# CANTensegrityBoard.net
KiCad netlist of a schematic drawn in EAGLE
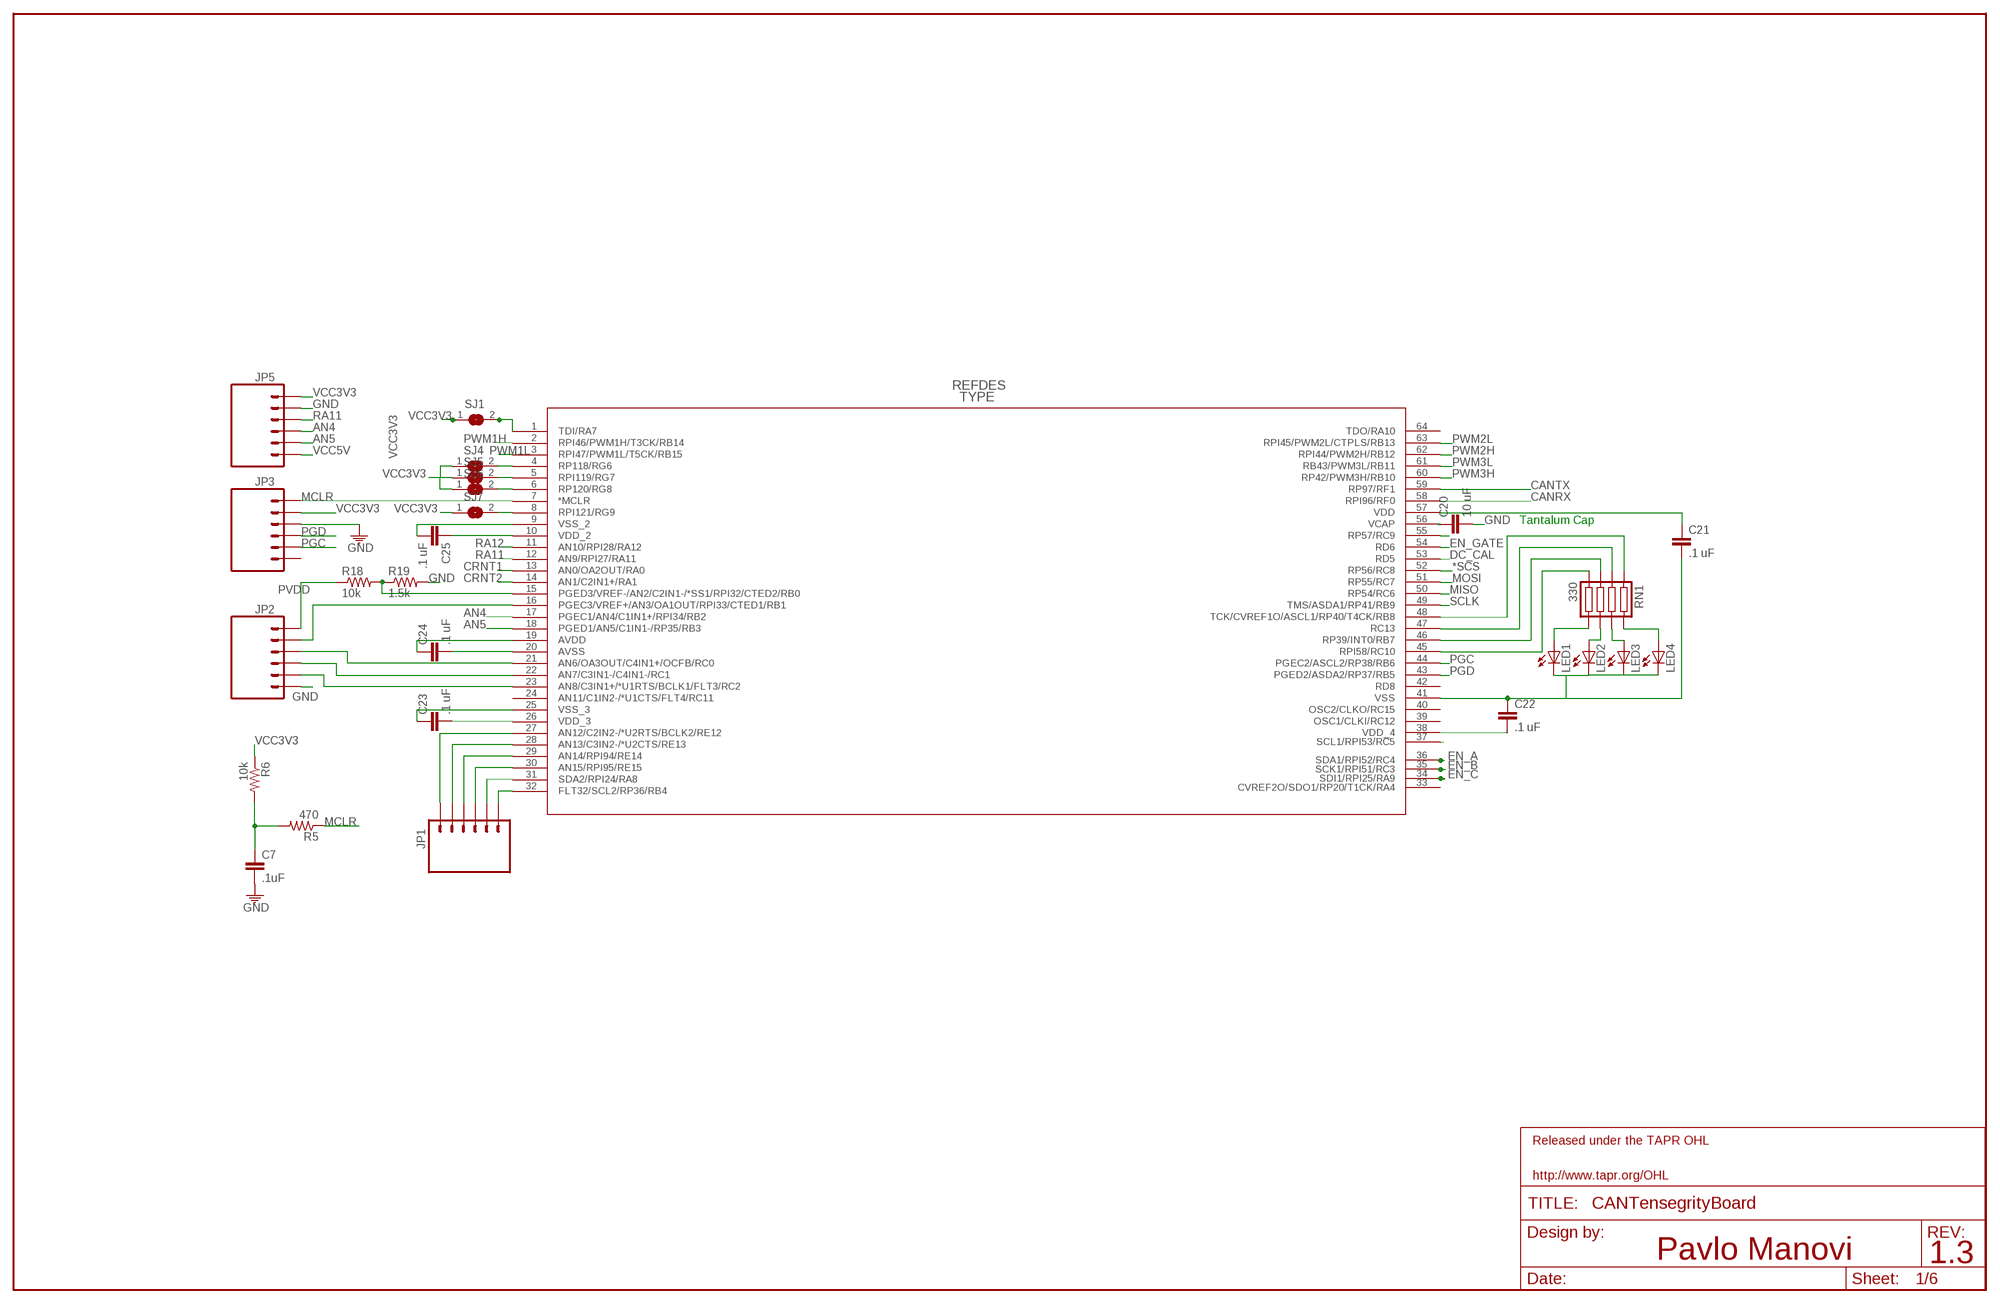
[diagram p0: schematic, sheet 1]
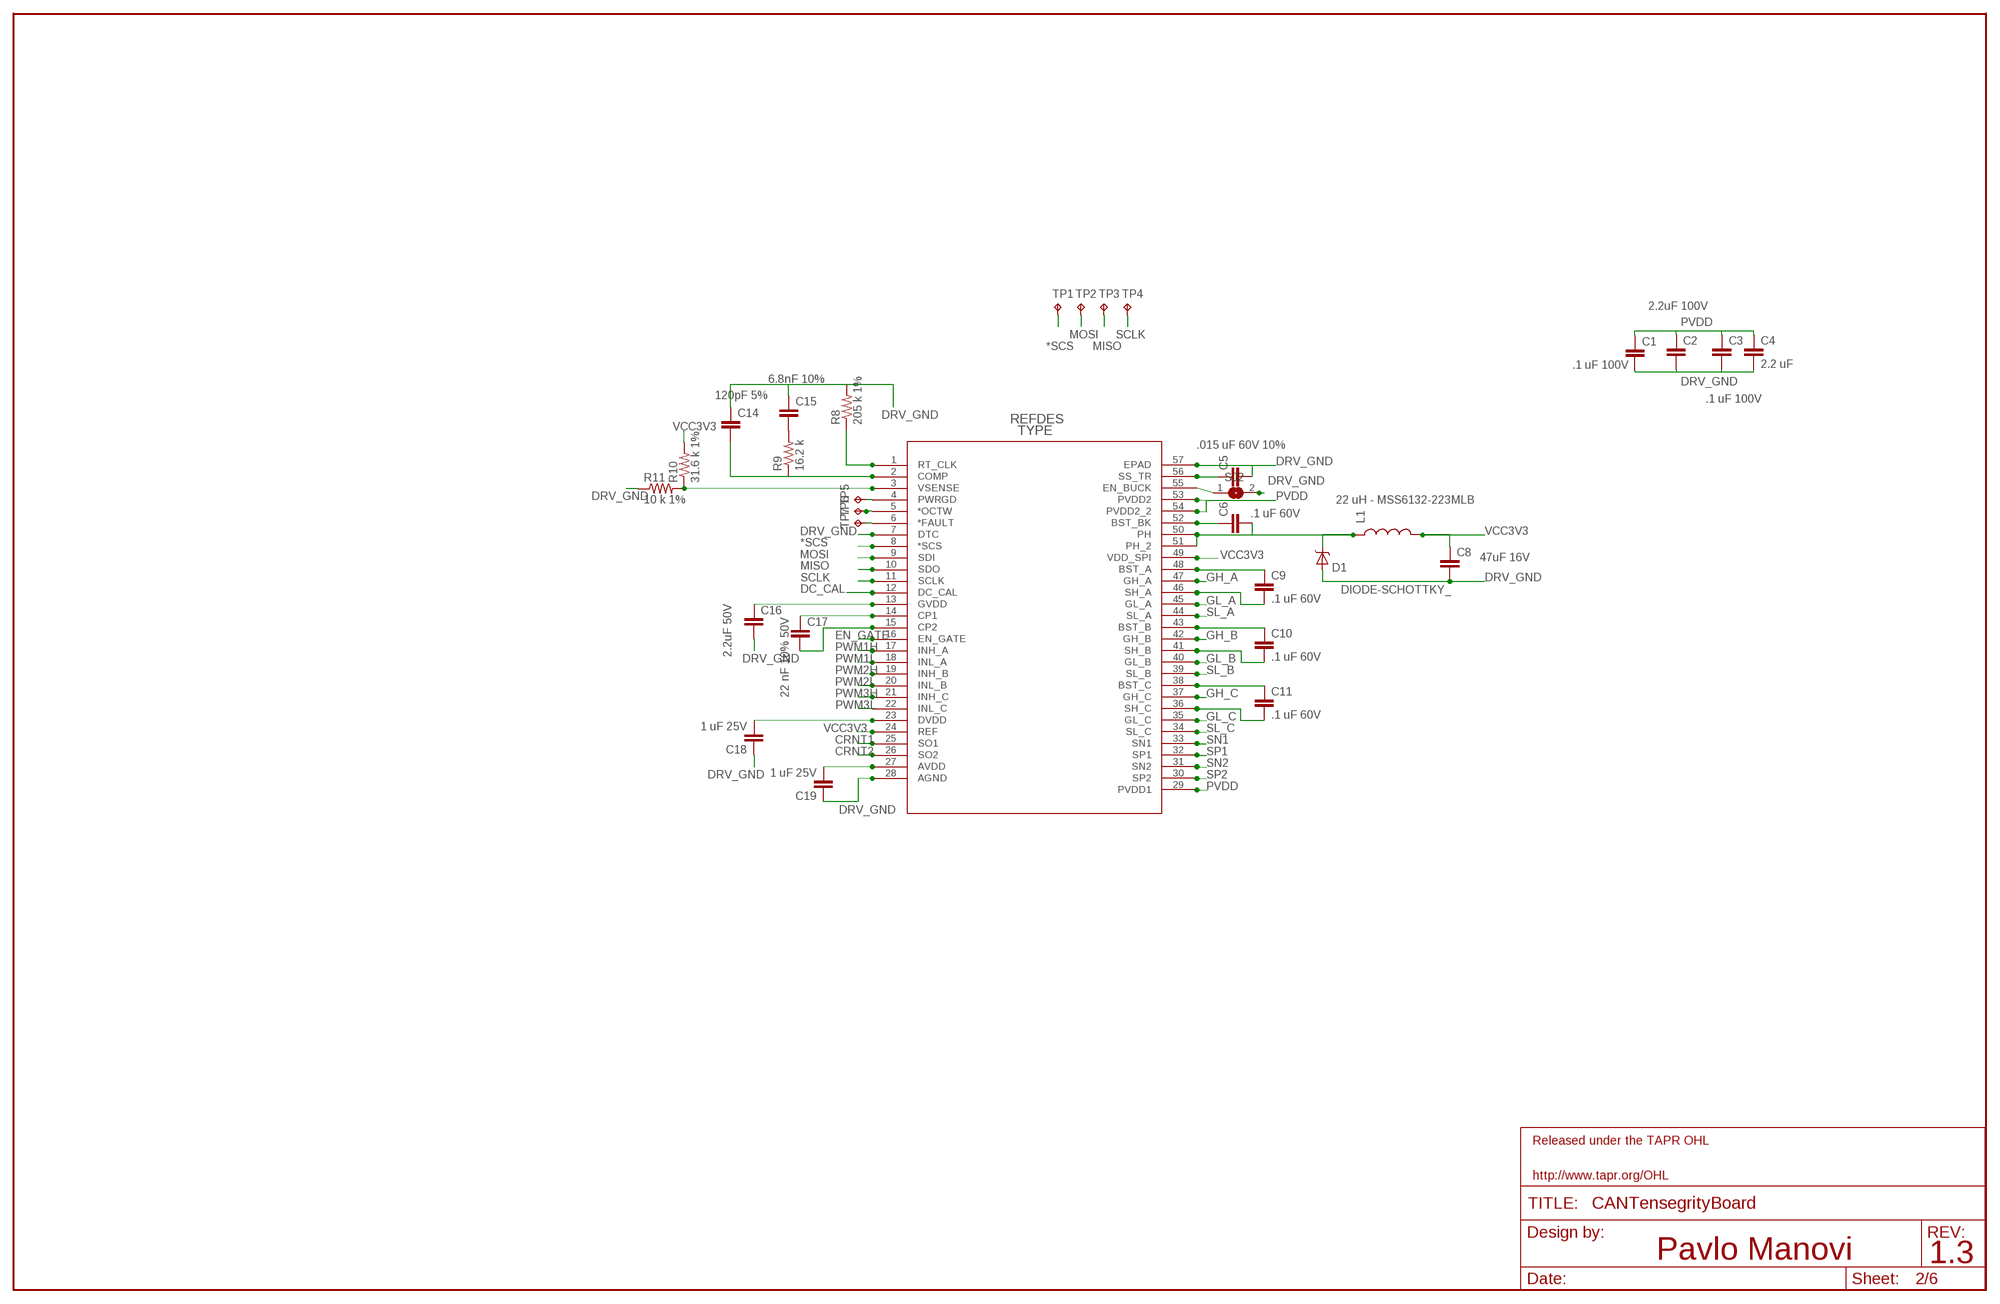
[diagram p1: schematic, sheet 2]
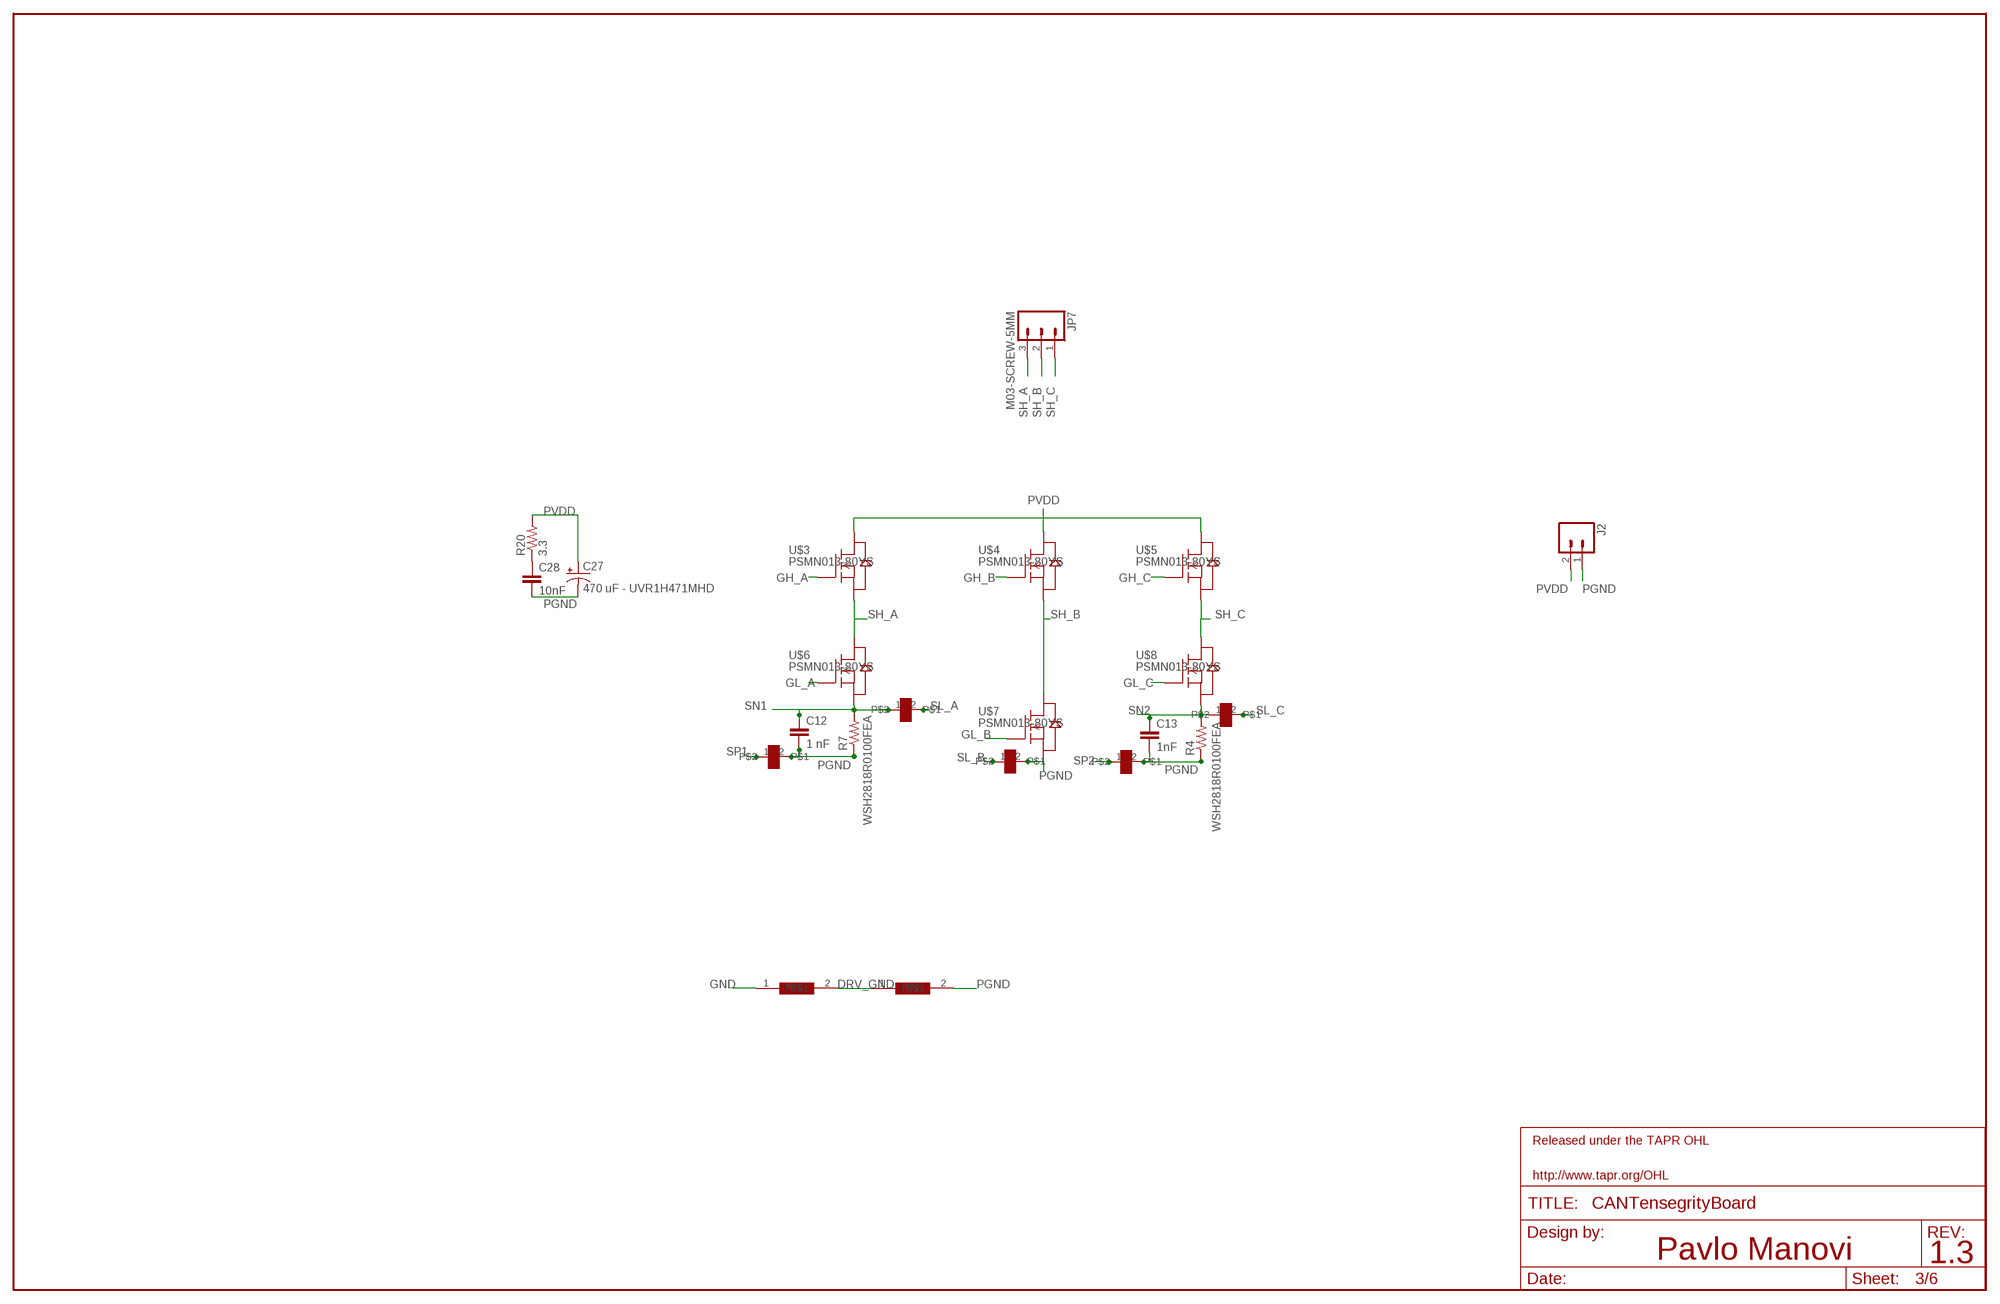
[diagram p2: schematic, sheet 3]
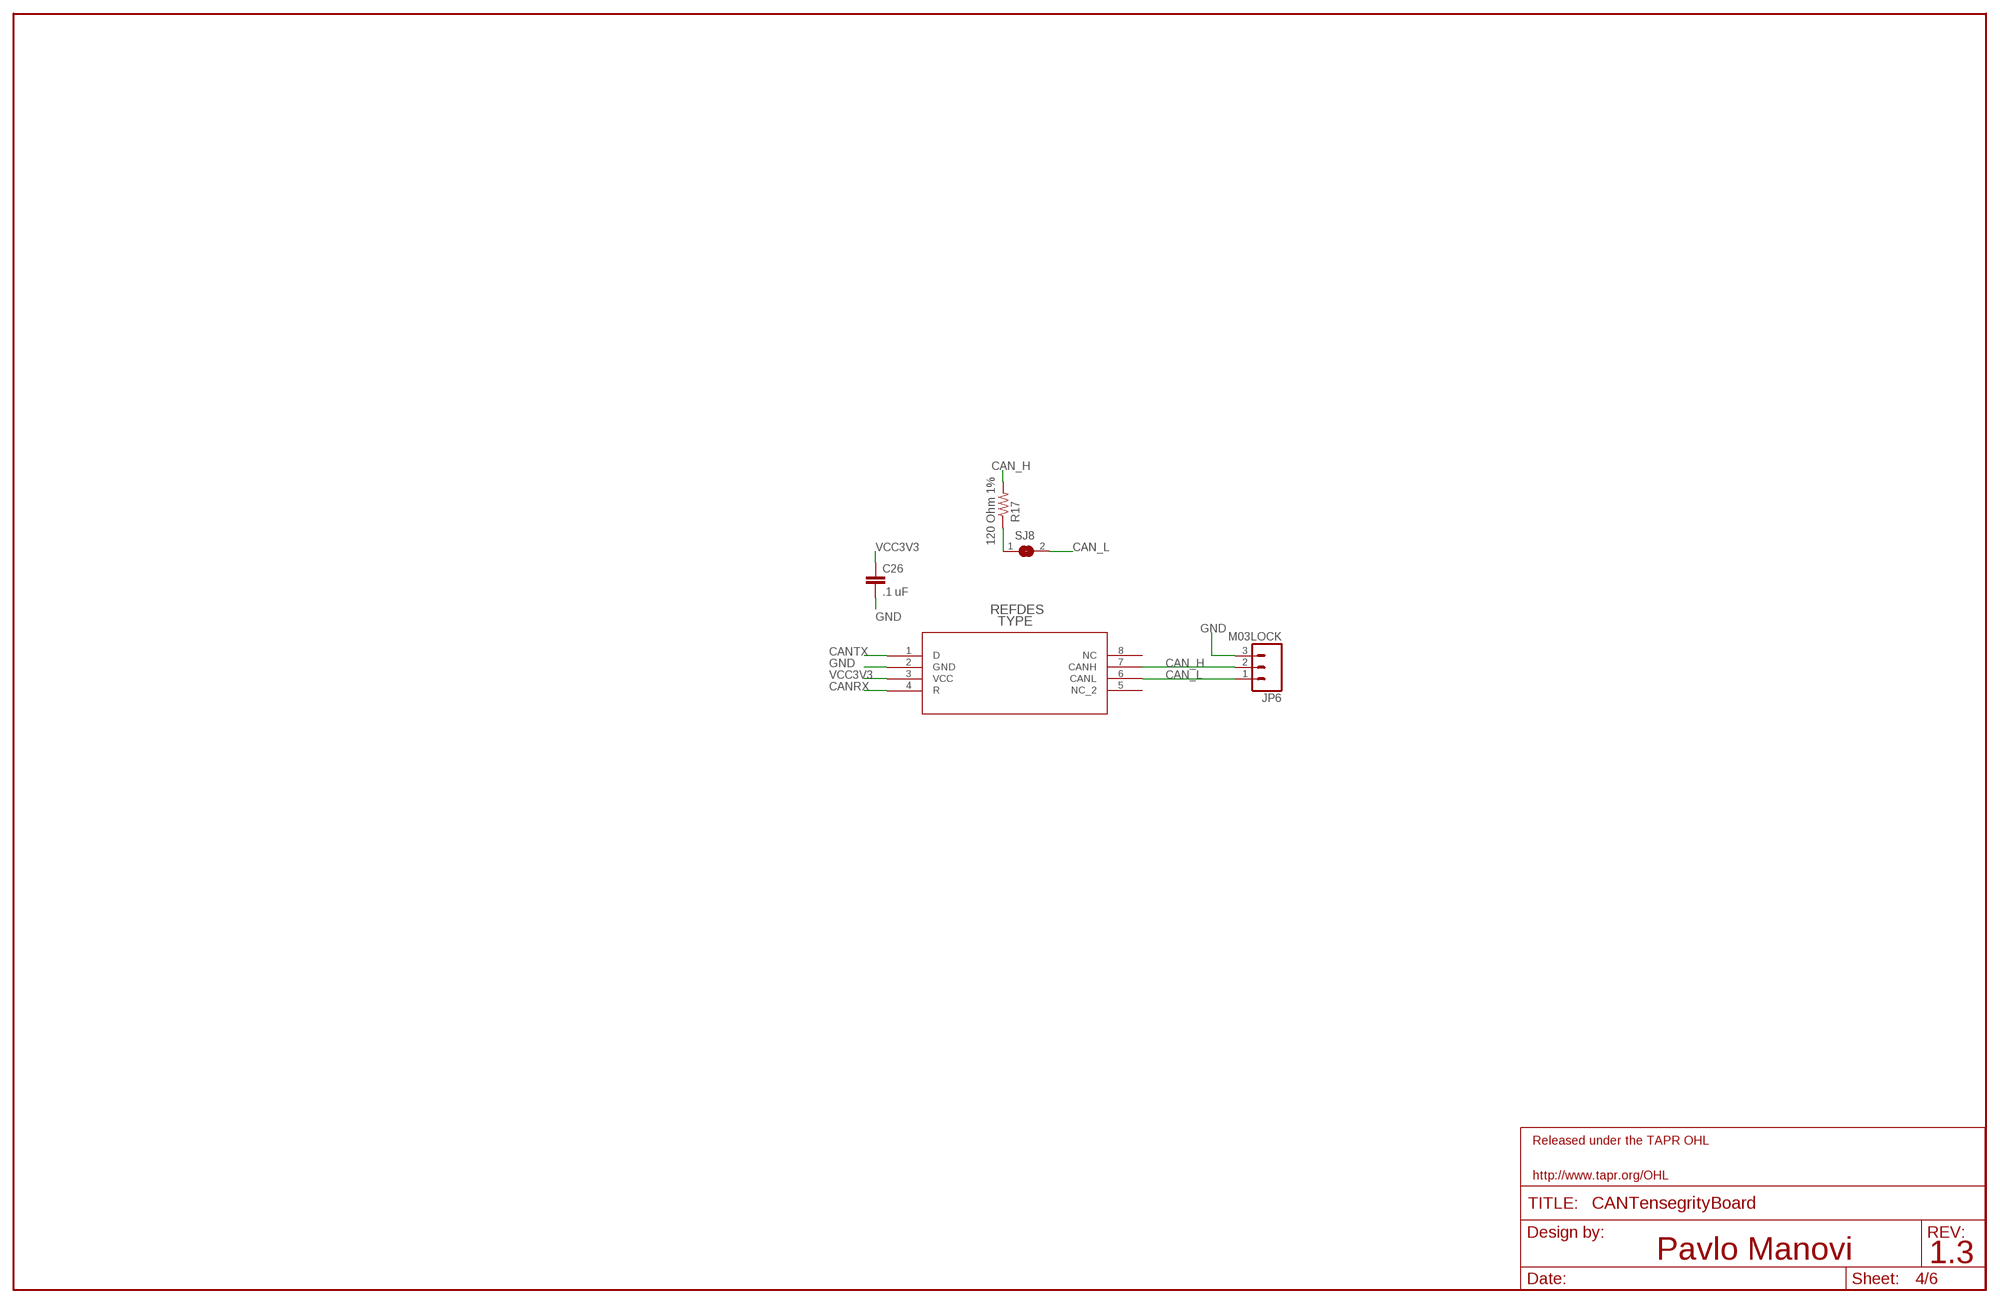
[diagram p3: schematic, sheet 4]
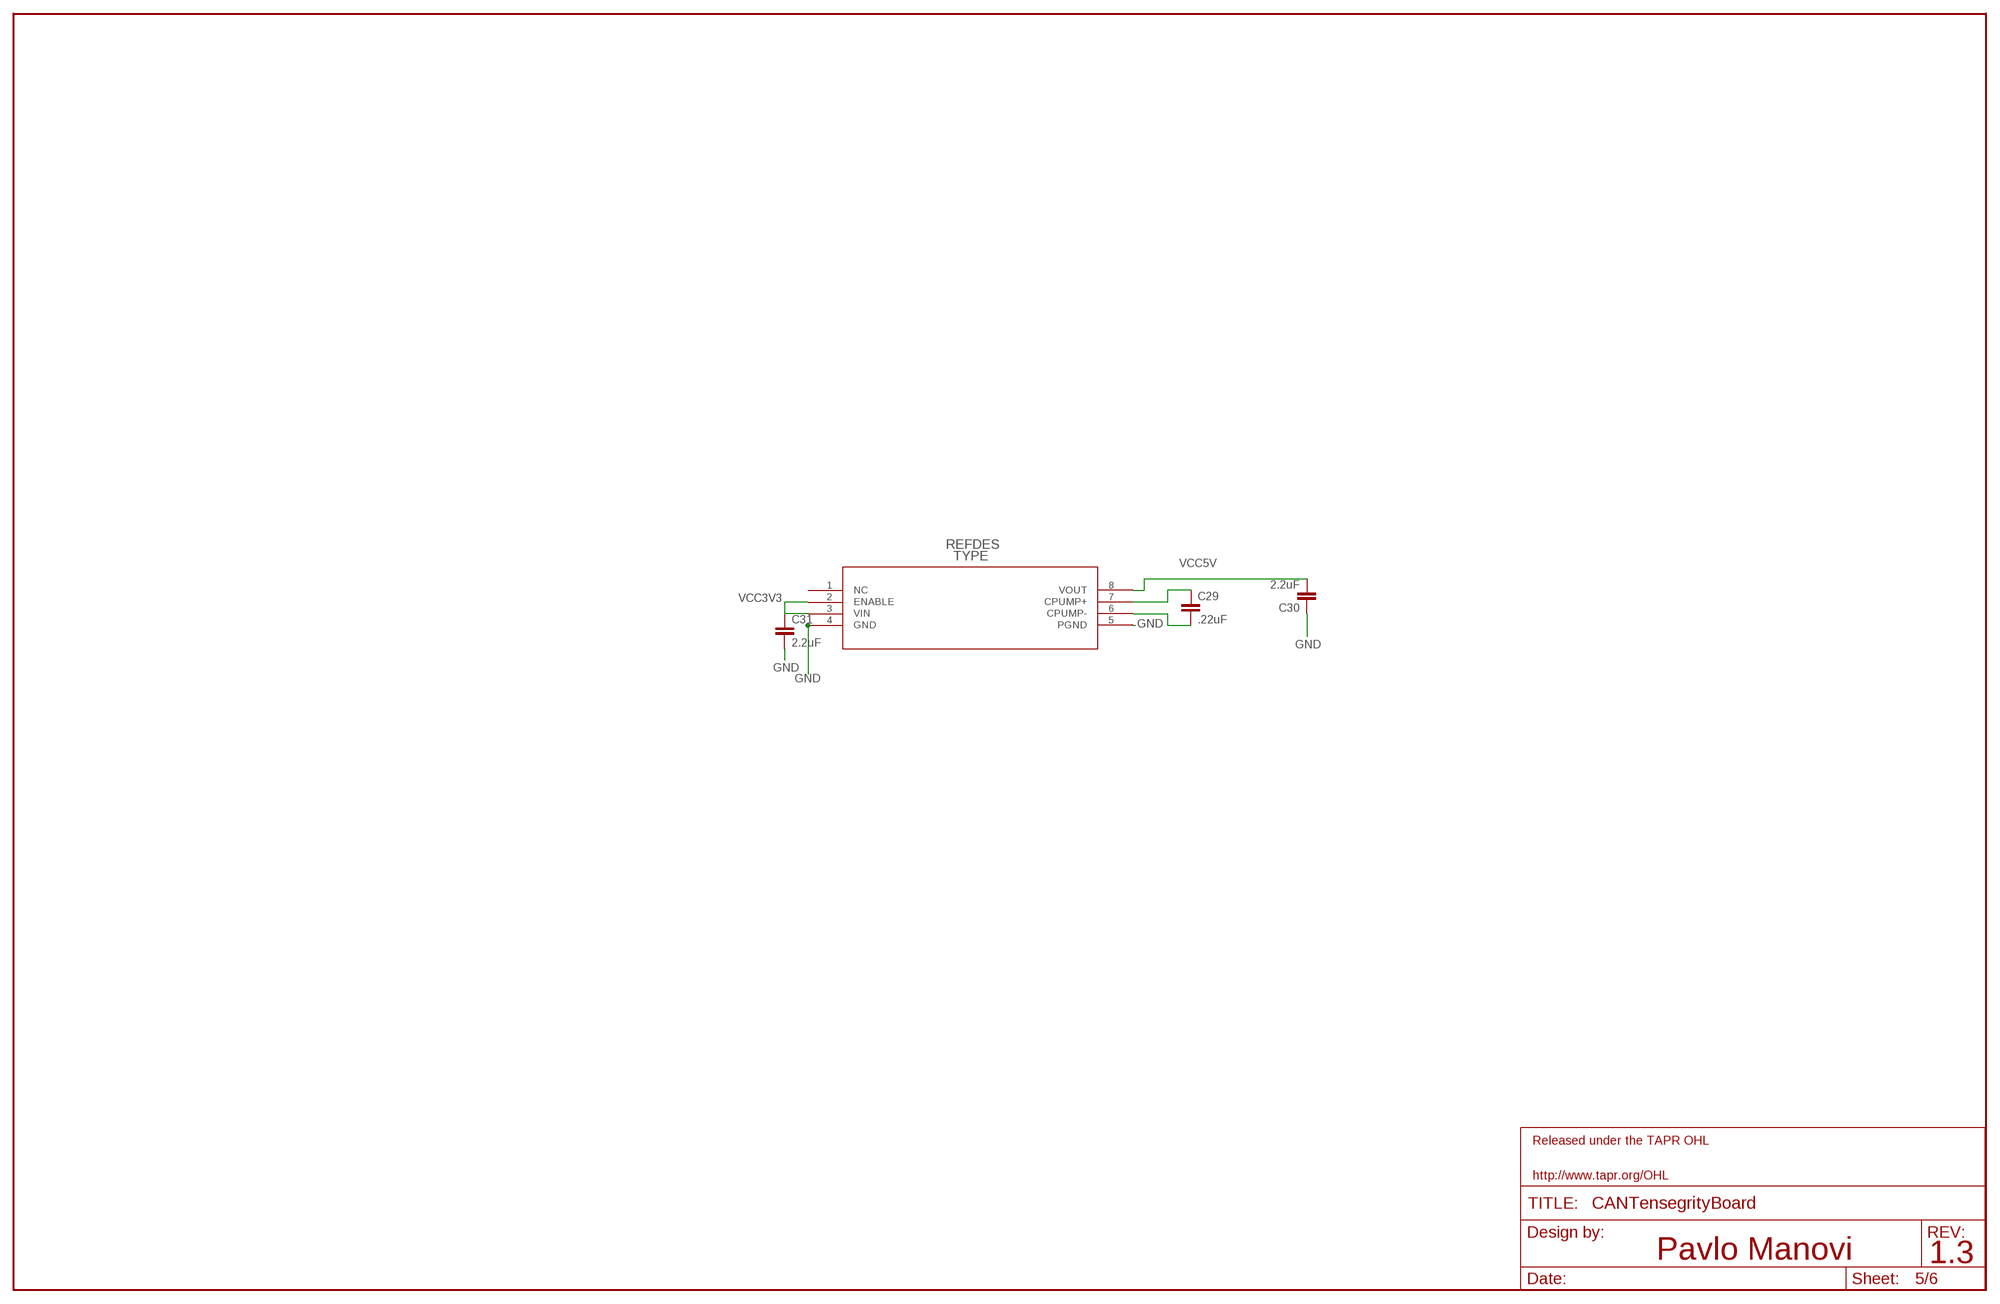
[diagram p4: schematic, sheet 5]
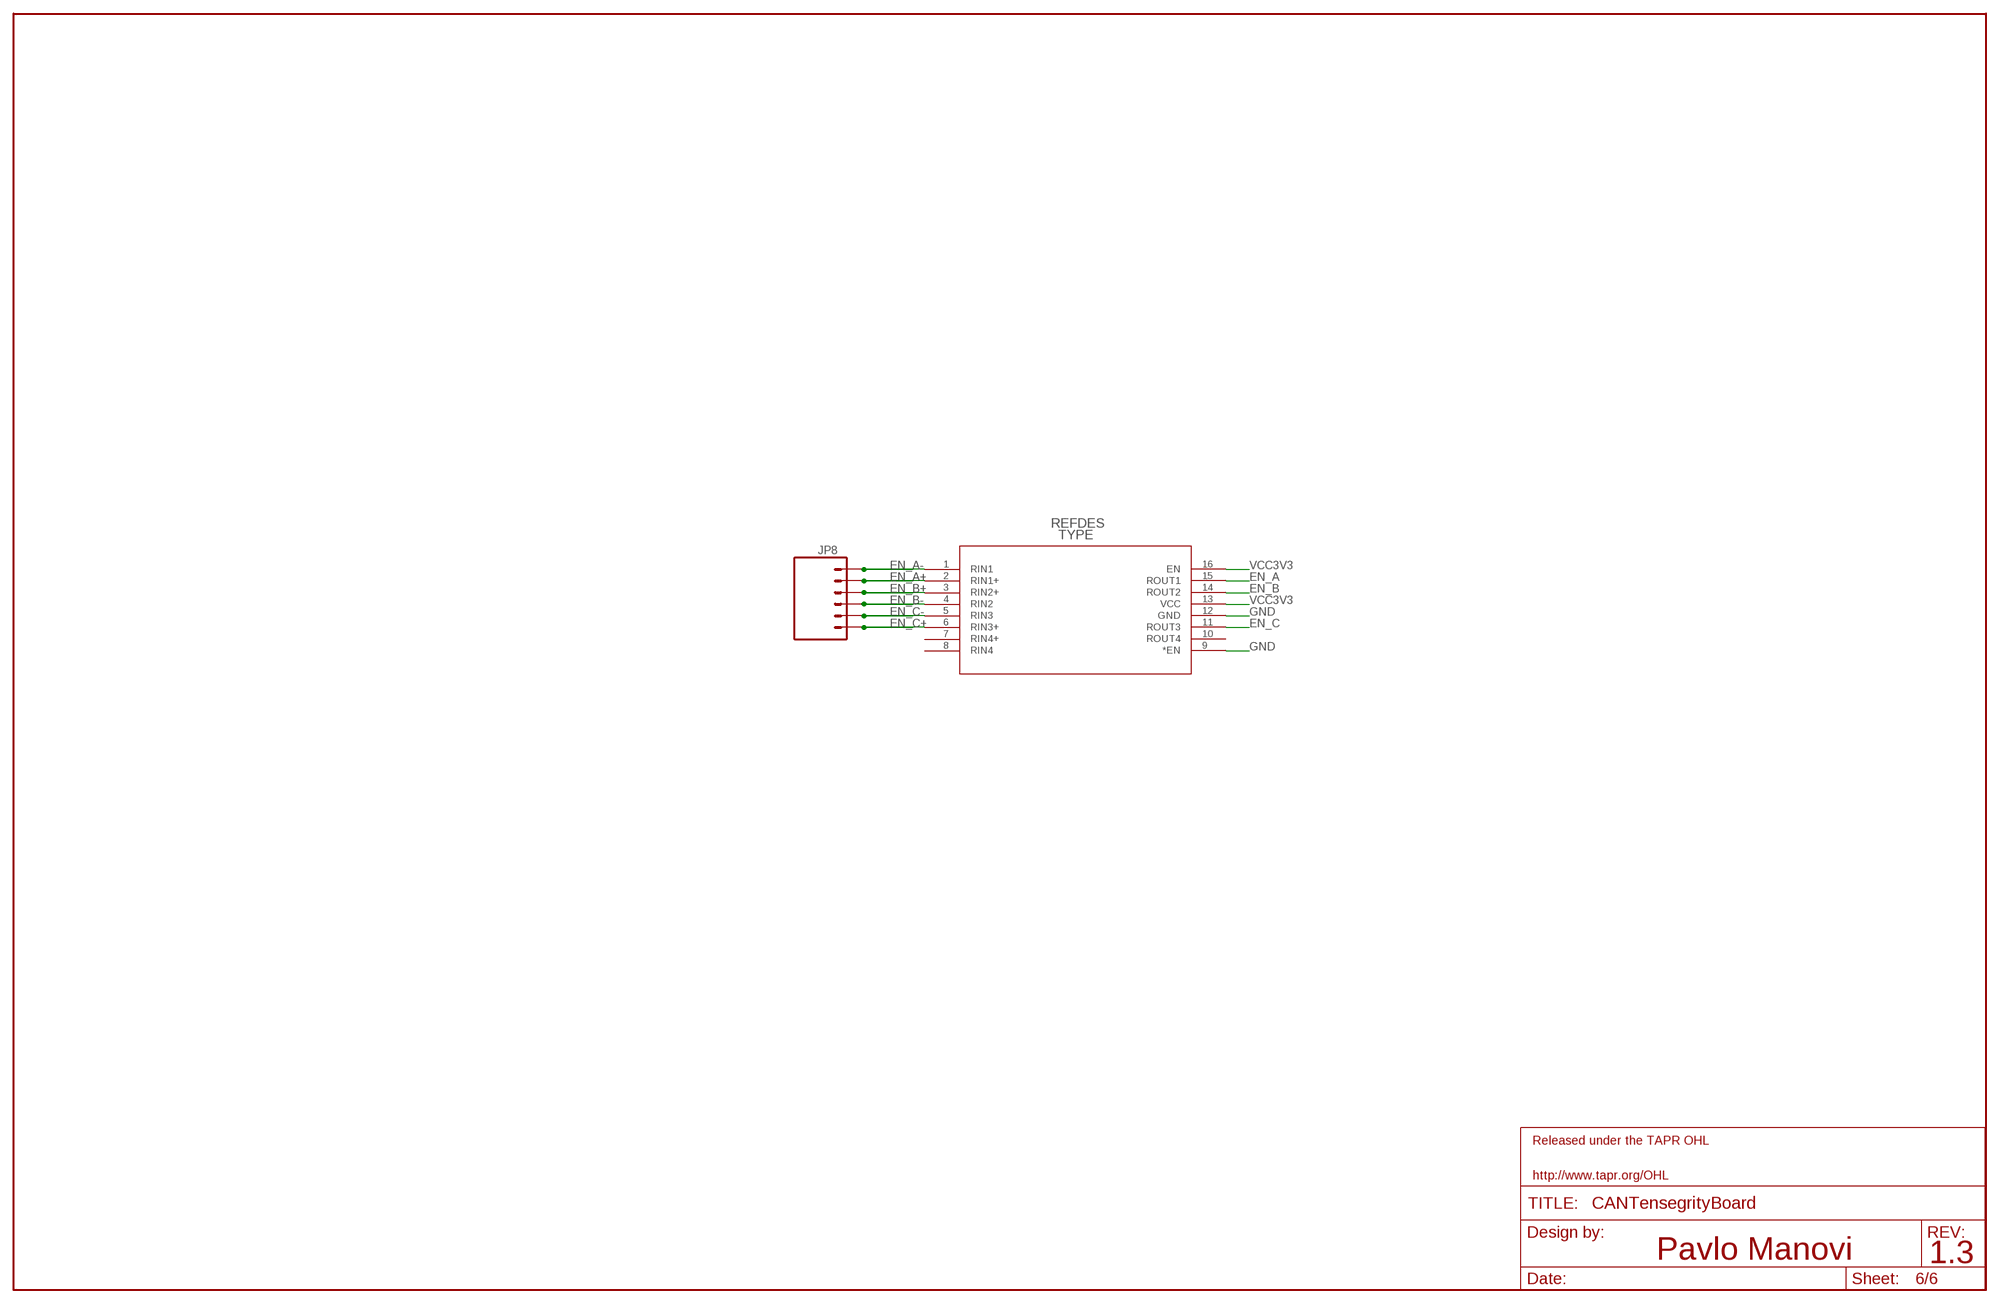
[diagram p5: schematic, sheet 6]

(export (version "E")
  (design (tool "Eeschema 10.0.6"))
  (components
    (comp (ref "C7")
      (value ".1uF")
      (footprint "eagle-import:0805")
      (libsource (lib "eagle-import") (part "CAP0805"))
    )
    (comp (ref "C20")
      (value "10 uF")
      (footprint "eagle-import:1206")
      (libsource (lib "eagle-import") (part "CAP1206"))
    )
    (comp (ref "C21")
      (value ".1 uF")
      (footprint "eagle-import:0805")
      (libsource (lib "eagle-import") (part "CAP0805"))
    )
    (comp (ref "C22")
      (value ".1 uF")
      (footprint "eagle-import:0805")
      (libsource (lib "eagle-import") (part "CAP0805"))
    )
    (comp (ref "C23")
      (value ".1 uF")
      (footprint "eagle-import:0805")
      (libsource (lib "eagle-import") (part "CAP0805"))
    )
    (comp (ref "C24")
      (value ".1 uF")
      (footprint "eagle-import:0805")
      (libsource (lib "eagle-import") (part "CAP0805"))
    )
    (comp (ref "C25")
      (value ".1 uF")
      (footprint "eagle-import:0805")
      (libsource (lib "eagle-import") (part "CAP0805"))
    )
    (comp (ref "JP1")
      (value "M06SIP")
      (footprint "eagle-import:1X06")
      (libsource (lib "eagle-import") (part "M06SIP"))
    )
    (comp (ref "JP2")
      (value "M06SIP")
      (footprint "eagle-import:1X06")
      (libsource (lib "eagle-import") (part "M06SIP"))
    )
    (comp (ref "JP3")
      (value "M06LOCK")
      (footprint "eagle-import:1X06_LOCK")
      (libsource (lib "eagle-import") (part "CMPE118lib_M06LOCK"))
    )
    (comp (ref "JP5")
      (value "M06LOCK")
      (footprint "eagle-import:1X06_LOCK")
      (libsource (lib "eagle-import") (part "CMPE118lib_M06LOCK"))
    )
    (comp (ref "LED1")
      (value "LED0805")
      (footprint "eagle-import:LED-0805")
      (libsource (lib "eagle-import") (part "LED0805"))
    )
    (comp (ref "LED2")
      (value "LED0805")
      (footprint "eagle-import:LED-0805")
      (libsource (lib "eagle-import") (part "LED0805"))
    )
    (comp (ref "LED3")
      (value "LED0805")
      (footprint "eagle-import:LED-0805")
      (libsource (lib "eagle-import") (part "LED0805"))
    )
    (comp (ref "LED4")
      (value "LED0805")
      (footprint "eagle-import:LED-0805")
      (libsource (lib "eagle-import") (part "LED0805"))
    )
    (comp (ref "R5")
      (value "470")
      (footprint "eagle-import:0805")
      (libsource (lib "eagle-import") (part "CMPE118lib_RESISTOR0805-RES"))
    )
    (comp (ref "R6")
      (value "10k")
      (footprint "eagle-import:0805")
      (libsource (lib "eagle-import") (part "CMPE118lib_RESISTOR0805-RES"))
    )
    (comp (ref "R18")
      (value "10k")
      (footprint "eagle-import:0805")
      (libsource (lib "eagle-import") (part "RESISTOR0805-RES"))
    )
    (comp (ref "R19")
      (value "1.5k")
      (footprint "eagle-import:0805")
      (libsource (lib "eagle-import") (part "RESISTOR0805-RES"))
    )
    (comp (ref "RN1")
      (value "330")
      (footprint "eagle-import:EXB-38V271JV")
      (libsource (lib "eagle-import") (part "RESISTOR_ARRAY-4"))
    )
    (comp (ref "SJ1") (value "SJ") (footprint "eagle-import:SJ") (libsource (lib "eagle-import") (part "SJ")))
    (comp (ref "SJ4") (value "SJ") (footprint "eagle-import:SJ") (libsource (lib "eagle-import") (part "SJ")))
    (comp (ref "SJ5") (value "SJ") (footprint "eagle-import:SJ") (libsource (lib "eagle-import") (part "SJ")))
    (comp (ref "SJ6") (value "SJ") (footprint "eagle-import:SJ") (libsource (lib "eagle-import") (part "SJ")))
    (comp (ref "SJ7") (value "SJ") (footprint "eagle-import:SJ") (libsource (lib "eagle-import") (part "SJ")))
    (comp (ref "U$1")
      (value "DSPIC33EP128MC502-I/SS")
      (footprint "eagle-import:QFP64-10X10MC")
      (libsource (lib "eagle-import") (part "DSPIC33EP256MC50"))
    )
    (comp (ref "C26")
      (value ".1 uF")
      (footprint "eagle-import:0805")
      (libsource (lib "eagle-import") (part "CAP0805"))
    )
    (comp (ref "JP6")
      (value "M03LOCK")
      (footprint "eagle-import:1X03_LOCK")
      (libsource (lib "eagle-import") (part "M03LOCK"))
    )
    (comp (ref "R17")
      (value "120 Ohm 1%")
      (footprint "eagle-import:0805")
      (libsource (lib "eagle-import") (part "RESISTOR0805-RES"))
    )
    (comp (ref "SJ8") (value "SJ") (footprint "eagle-import:SJ") (libsource (lib "eagle-import") (part "SJ")))
    (comp (ref "U2")
      (value "SN65HVD232_D_8")
      (footprint "eagle-import:D8")
      (libsource (lib "eagle-import") (part "SN65HVD232_D_8"))
    )
    (comp (ref "C1")
      (value ".1 uF 100V")
      (footprint "eagle-import:0805")
      (libsource (lib "eagle-import") (part "CAP0805"))
    )
    (comp (ref "C2")
      (value "2.2uF 100V")
      (footprint "eagle-import:1206")
      (libsource (lib "eagle-import") (part "CAP1206"))
    )
    (comp (ref "C3")
      (value ".1 uF 100V")
      (footprint "eagle-import:0805")
      (libsource (lib "eagle-import") (part "CAP0805"))
    )
    (comp (ref "C4")
      (value "2.2 uF")
      (footprint "eagle-import:1206")
      (libsource (lib "eagle-import") (part "CAP1206"))
    )
    (comp (ref "C5")
      (value ".015 uF 60V 10%")
      (footprint "eagle-import:0805")
      (libsource (lib "eagle-import") (part "CAP0805"))
    )
    (comp (ref "C6")
      (value ".1 uF 60V")
      (footprint "eagle-import:0805")
      (libsource (lib "eagle-import") (part "CAP0805"))
    )
    (comp (ref "C8")
      (value "47uF 16V")
      (footprint "eagle-import:1206")
      (libsource (lib "eagle-import") (part "CAP1206"))
    )
    (comp (ref "C9")
      (value ".1 uF 60V")
      (footprint "eagle-import:0805")
      (libsource (lib "eagle-import") (part "CAP0805"))
    )
    (comp (ref "C10")
      (value ".1 uF 60V")
      (footprint "eagle-import:0805")
      (libsource (lib "eagle-import") (part "CAP0805"))
    )
    (comp (ref "C11")
      (value ".1 uF 60V")
      (footprint "eagle-import:0805")
      (libsource (lib "eagle-import") (part "CAP0805"))
    )
    (comp (ref "C14")
      (value "120pF 5%")
      (footprint "eagle-import:0805")
      (libsource (lib "eagle-import") (part "CAP0805"))
    )
    (comp (ref "C15")
      (value "6.8nF 10%")
      (footprint "eagle-import:0805")
      (libsource (lib "eagle-import") (part "CAP0805"))
    )
    (comp (ref "C16")
      (value "2.2uF 50V")
      (footprint "eagle-import:1206")
      (libsource (lib "eagle-import") (part "CAP1206"))
    )
    (comp (ref "C17")
      (value "22 nF 10% 50V")
      (footprint "eagle-import:0805")
      (libsource (lib "eagle-import") (part "CAP0805"))
    )
    (comp (ref "C18")
      (value "1 uF 25V")
      (footprint "eagle-import:0805")
      (libsource (lib "eagle-import") (part "CAP0805"))
    )
    (comp (ref "C19")
      (value "1 uF 25V")
      (footprint "eagle-import:0805")
      (libsource (lib "eagle-import") (part "CAP0805"))
    )
    (comp (ref "D1")
      (value "DIODE-SCHOTTKY_")
      (footprint "eagle-import:SMA-DIODE")
      (libsource (lib "eagle-import") (part "DIODE-SCHOTTKY_"))
    )
    (comp (ref "L1")
      (value "22 uH - MSS6132-223MLB")
      (footprint "eagle-import:MSS6132")
      (libsource (lib "eagle-import") (part "INDUCTOR"))
    )
    (comp (ref "R8")
      (value "205 k 1%")
      (footprint "eagle-import:0805")
      (libsource (lib "eagle-import") (part "RESISTOR0805-RES"))
    )
    (comp (ref "R9")
      (value "16.2 k")
      (footprint "eagle-import:0805")
      (libsource (lib "eagle-import") (part "RESISTOR0805-RES"))
    )
    (comp (ref "R10")
      (value "31.6 k 1%")
      (footprint "eagle-import:0805")
      (libsource (lib "eagle-import") (part "RESISTOR0805-RES"))
    )
    (comp (ref "R11")
      (value "10 k 1%")
      (footprint "eagle-import:0805")
      (libsource (lib "eagle-import") (part "RESISTOR0805-RES"))
    )
    (comp (ref "SJ2") (value "SJ") (footprint "eagle-import:SJ") (libsource (lib "eagle-import") (part "SJ")))
    (comp (ref "TP1")
      (value "TPTP06R")
      (footprint "eagle-import:TP06R")
      (libsource (lib "eagle-import") (part "TPTP06R"))
    )
    (comp (ref "TP2")
      (value "TPTP06R")
      (footprint "eagle-import:TP06R")
      (libsource (lib "eagle-import") (part "TPTP06R"))
    )
    (comp (ref "TP3")
      (value "TPTP06R")
      (footprint "eagle-import:TP06R")
      (libsource (lib "eagle-import") (part "TPTP06R"))
    )
    (comp (ref "TP4")
      (value "TPTP06R")
      (footprint "eagle-import:TP06R")
      (libsource (lib "eagle-import") (part "TPTP06R"))
    )
    (comp (ref "TP5")
      (value "TPTP06R")
      (footprint "eagle-import:TP06R")
      (libsource (lib "eagle-import") (part "TPTP06R"))
    )
    (comp (ref "TP6")
      (value "TPTP06R")
      (footprint "eagle-import:TP06R")
      (libsource (lib "eagle-import") (part "TPTP06R"))
    )
    (comp (ref "TP7")
      (value "TPTP06R")
      (footprint "eagle-import:TP06R")
      (libsource (lib "eagle-import") (part "TPTP06R"))
    )
    (comp (ref "U$2")
      (value "DRV8301")
      (footprint "eagle-import:DCA56_6P35X3P61")
      (libsource (lib "eagle-import") (part "DRV8301"))
    )
    (comp (ref "C12")
      (value "1 nF")
      (footprint "eagle-import:0805")
      (libsource (lib "eagle-import") (part "CAP0805"))
    )
    (comp (ref "C13")
      (value "1nF")
      (footprint "eagle-import:0805")
      (libsource (lib "eagle-import") (part "CAP0805"))
    )
    (comp (ref "C27")
      (value "470 uF - UVR1H471MHD")
      (footprint "eagle-import:CPOL-RADIAL-1000UF-25V")
      (libsource (lib "eagle-import") (part "CAP_POLPTH4"))
    )
    (comp (ref "C28")
      (value "10nF")
      (footprint "eagle-import:0805")
      (libsource (lib "eagle-import") (part "CAP0805"))
    )
    (comp (ref "J2")
      (value "M02PTH4")
      (footprint "eagle-import:1X02_XTRA_BIG")
      (libsource (lib "eagle-import") (part "M02PTH4"))
    )
    (comp (ref "JP7")
      (value "M03-SCREW-5MM")
      (footprint "eagle-import:SCREWTERMINAL-5MM-3")
      (libsource (lib "eagle-import") (part "pavlo_M03-SCREW-5MM"))
    )
    (comp (ref "R4")
      (value "WSH2818R0100FEA")
      (footprint "eagle-import:SMT-REF")
      (libsource (lib "eagle-import") (part "RESISTOR"))
    )
    (comp (ref "R7")
      (value "WSH2818R0100FEA")
      (footprint "eagle-import:SMT-REF")
      (libsource (lib "eagle-import") (part "RESISTOR"))
    )
    (comp (ref "R20")
      (value "3.3")
      (footprint "eagle-import:0805")
      (libsource (lib "eagle-import") (part "RESISTOR0805-RES"))
    )
    (comp (ref "U$3")
      (value "PSMN013-80YS")
      (footprint "eagle-import:TO127P600X120-5N")
      (libsource (lib "eagle-import") (part "PSMN013-80YS"))
    )
    (comp (ref "U$4")
      (value "PSMN013-80YS")
      (footprint "eagle-import:TO127P600X120-5N")
      (libsource (lib "eagle-import") (part "PSMN013-80YS"))
    )
    (comp (ref "U$5")
      (value "PSMN013-80YS")
      (footprint "eagle-import:TO127P600X120-5N")
      (libsource (lib "eagle-import") (part "PSMN013-80YS"))
    )
    (comp (ref "U$6")
      (value "PSMN013-80YS")
      (footprint "eagle-import:TO127P600X120-5N")
      (libsource (lib "eagle-import") (part "PSMN013-80YS"))
    )
    (comp (ref "U$7")
      (value "PSMN013-80YS")
      (footprint "eagle-import:TO127P600X120-5N")
      (libsource (lib "eagle-import") (part "PSMN013-80YS"))
    )
    (comp (ref "U$8")
      (value "PSMN013-80YS")
      (footprint "eagle-import:TO127P600X120-5N")
      (libsource (lib "eagle-import") (part "PSMN013-80YS"))
    )
    (comp (ref "U9")
      (value "H1206T500R-10")
      (footprint "eagle-import:1206")
      (libsource (lib "eagle-import") (part "H1206T500R-10"))
    )
    (comp (ref "U10")
      (value "H1206T500R-10")
      (footprint "eagle-import:1206")
      (libsource (lib "eagle-import") (part "H1206T500R-10"))
    )
    (comp (ref "U11")
      (value "MH1608-600Y")
      (footprint "eagle-import:0603")
      (libsource (lib "eagle-import") (part "MH1608-600Y"))
    )
    (comp (ref "U12")
      (value "MH1608-600Y")
      (footprint "eagle-import:0603")
      (libsource (lib "eagle-import") (part "MH1608-600Y"))
    )
    (comp (ref "U13")
      (value "MH1608-600Y")
      (footprint "eagle-import:0603")
      (libsource (lib "eagle-import") (part "MH1608-600Y"))
    )
    (comp (ref "U14")
      (value "MH1608-600Y")
      (footprint "eagle-import:0603")
      (libsource (lib "eagle-import") (part "MH1608-600Y"))
    )
    (comp (ref "U15")
      (value "MH1608-600Y")
      (footprint "eagle-import:0603")
      (libsource (lib "eagle-import") (part "MH1608-600Y"))
    )
    (comp (ref "C29")
      (value ".22uF")
      (footprint "eagle-import:0805")
      (libsource (lib "eagle-import") (part "CAP0805"))
    )
    (comp (ref "C30")
      (value "2.2uF")
      (footprint "eagle-import:0805")
      (libsource (lib "eagle-import") (part "CAP0805"))
    )
    (comp (ref "C31")
      (value "2.2uF")
      (footprint "eagle-import:0805")
      (libsource (lib "eagle-import") (part "CAP0805"))
    )
    (comp (ref "U1")
      (value "REG711-5_DGK_8")
      (footprint "eagle-import:DGK8")
      (libsource (lib "eagle-import") (part "REG711-5_DGK_8"))
    )
    (comp (ref "JP8")
      (value "M06SIP_LOCK")
      (footprint "eagle-import:1X06-SIP_LOCK")
      (libsource (lib "eagle-import") (part "M06SIP_LOCK"))
    )
    (comp (ref "U3")
      (value "SN65LVDT348_PW_1")
      (footprint "eagle-import:PW16")
      (libsource (lib "eagle-import") (part "SN65LVDT348_PW_1"))
    )
  )
  (nets
    (net (code "1") (name "*SCS") (class "Default")
      (node (ref "TP1") (pin "TP") (pinfunction "TP_TP") (pintype "input"))
      (node (ref "U$1") (pin "52") (pinfunction "RP56/RC8_52") (pintype "passive"))
      (node (ref "U$2") (pin "8") (pinfunction "*SCS_8") (pintype "passive"))
    )
    (net (code "2") (name "AN4") (class "Default")
      (node (ref "JP5") (pin "4") (pinfunction "4_4") (pintype "passive"))
      (node (ref "U$1") (pin "17") (pinfunction "PGEC1/AN4/C1IN1+/RPI34/RB2_17") (pintype "passive"))
    )
    (net (code "3") (name "AN5") (class "Default")
      (node (ref "JP5") (pin "5") (pinfunction "5_5") (pintype "passive"))
      (node (ref "U$1") (pin "18") (pinfunction "PGED1/AN5/C1IN1-/RP35/RB3_18") (pintype "passive"))
    )
    (net (code "4") (name "CANRX") (class "Default")
      (node (ref "U$1") (pin "58") (pinfunction "RPI96/RF0_58") (pintype "passive"))
      (node (ref "U2") (pin "4") (pinfunction "R_4") (pintype "passive"))
    )
    (net (code "5") (name "CANTX") (class "Default")
      (node (ref "U$1") (pin "59") (pinfunction "RP97/RF1_59") (pintype "passive"))
      (node (ref "U2") (pin "1") (pinfunction "D_1") (pintype "passive"))
    )
    (net (code "6") (name "CAN_H") (class "Default")
      (node (ref "JP6") (pin "2") (pinfunction "2_2") (pintype "passive"))
      (node (ref "R17") (pin "2") (pinfunction "2_2") (pintype "passive"))
      (node (ref "U2") (pin "7") (pinfunction "CANH_7") (pintype "passive"))
    )
    (net (code "7") (name "CAN_L") (class "Default")
      (node (ref "JP6") (pin "1") (pinfunction "1_1") (pintype "passive"))
      (node (ref "SJ8") (pin "2") (pinfunction "2_2") (pintype "passive"))
      (node (ref "U2") (pin "6") (pinfunction "CANL_6") (pintype "passive"))
    )
    (net (code "8") (name "CRNT1") (class "Default")
      (node (ref "U$1") (pin "13") (pinfunction "AN0/OA2OUT/RA0_13") (pintype "passive"))
      (node (ref "U$2") (pin "25") (pinfunction "SO1_25") (pintype "passive"))
    )
    (net (code "9") (name "CRNT2") (class "Default")
      (node (ref "U$1") (pin "14") (pinfunction "AN1/C2IN1+/RA1_14") (pintype "passive"))
      (node (ref "U$2") (pin "26") (pinfunction "SO2_26") (pintype "passive"))
    )
    (net (code "10") (name "DC_CAL") (class "Default")
      (node (ref "U$1") (pin "53") (pinfunction "RD5_53") (pintype "passive"))
      (node (ref "U$2") (pin "12") (pinfunction "DC_CAL_12") (pintype "passive"))
    )
    (net (code "11") (name "DRV_GND") (class "Default")
      (node (ref "C1") (pin "2") (pinfunction "2_2") (pintype "passive"))
      (node (ref "C14") (pin "1") (pinfunction "1_1") (pintype "passive"))
      (node (ref "C15") (pin "1") (pinfunction "1_1") (pintype "passive"))
      (node (ref "C16") (pin "2") (pinfunction "2_2") (pintype "passive"))
      (node (ref "C18") (pin "1") (pinfunction "1_1") (pintype "passive"))
      (node (ref "C19") (pin "1") (pinfunction "1_1") (pintype "passive"))
      (node (ref "C2") (pin "2") (pinfunction "2_2") (pintype "passive"))
      (node (ref "C3") (pin "2") (pinfunction "2_2") (pintype "passive"))
      (node (ref "C4") (pin "2") (pinfunction "2_2") (pintype "passive"))
      (node (ref "C5") (pin "2") (pinfunction "2_2") (pintype "passive"))
      (node (ref "C8") (pin "2") (pinfunction "2_2") (pintype "passive"))
      (node (ref "D1") (pin "A") (pinfunction "A_A") (pintype "passive"))
      (node (ref "R11") (pin "1") (pinfunction "1_1") (pintype "passive"))
      (node (ref "R8") (pin "2") (pinfunction "2_2") (pintype "passive"))
      (node (ref "SJ2") (pin "2") (pinfunction "2_2") (pintype "passive"))
      (node (ref "U$2") (pin "28") (pinfunction "AGND_28") (pintype "passive"))
      (node (ref "U$2") (pin "57") (pinfunction "EPAD_57") (pintype "passive"))
      (node (ref "U$2") (pin "7") (pinfunction "DTC_7") (pintype "passive"))
      (node (ref "U10") (pin "1") (pinfunction "P$1_1") (pintype "bidirectional"))
      (node (ref "U9") (pin "2") (pinfunction "P$2_2") (pintype "bidirectional"))
    )
    (net (code "12") (name "EN_A") (class "Default")
      (node (ref "U$1") (pin "36") (pinfunction "SDA1/RPI52/RC4_36") (pintype "passive"))
      (node (ref "U3") (pin "15") (pinfunction "ROUT1_15") (pintype "passive"))
    )
    (net (code "13") (name "EN_A+") (class "Default")
      (node (ref "JP8") (pin "2") (pinfunction "2_2") (pintype "passive"))
      (node (ref "U3") (pin "2") (pinfunction "RIN1+_2") (pintype "passive"))
    )
    (net (code "14") (name "EN_A-") (class "Default")
      (node (ref "JP8") (pin "1") (pinfunction "1_1") (pintype "passive"))
      (node (ref "U3") (pin "1") (pinfunction "RIN1_1") (pintype "passive"))
    )
    (net (code "15") (name "EN_B") (class "Default")
      (node (ref "U$1") (pin "35") (pinfunction "SCK1/RPI51/RC3_35") (pintype "passive"))
      (node (ref "U3") (pin "14") (pinfunction "ROUT2_14") (pintype "passive"))
    )
    (net (code "16") (name "EN_B+") (class "Default")
      (node (ref "JP8") (pin "3") (pinfunction "3_3") (pintype "passive"))
      (node (ref "U3") (pin "3") (pinfunction "RIN2+_3") (pintype "passive"))
    )
    (net (code "17") (name "EN_B-") (class "Default")
      (node (ref "JP8") (pin "4") (pinfunction "4_4") (pintype "passive"))
      (node (ref "U3") (pin "4") (pinfunction "RIN2_4") (pintype "passive"))
    )
    (net (code "18") (name "EN_C") (class "Default")
      (node (ref "U$1") (pin "34") (pinfunction "SDI1/RPI25/RA9_34") (pintype "passive"))
      (node (ref "U3") (pin "11") (pinfunction "ROUT3_11") (pintype "passive"))
    )
    (net (code "19") (name "EN_C+") (class "Default")
      (node (ref "JP8") (pin "6") (pinfunction "6_6") (pintype "passive"))
      (node (ref "U3") (pin "6") (pinfunction "RIN3+_6") (pintype "passive"))
    )
    (net (code "20") (name "EN_C-") (class "Default")
      (node (ref "JP8") (pin "5") (pinfunction "5_5") (pintype "passive"))
      (node (ref "U3") (pin "5") (pinfunction "RIN3_5") (pintype "passive"))
    )
    (net (code "21") (name "EN_GATE") (class "Default")
      (node (ref "U$1") (pin "54") (pinfunction "RD6_54") (pintype "passive"))
      (node (ref "U$2") (pin "16") (pinfunction "EN_GATE_16") (pintype "passive"))
    )
    (net (code "22") (name "GH_A") (class "Default")
      (node (ref "U$2") (pin "47") (pinfunction "GH_A_47") (pintype "passive"))
      (node (ref "U$3") (pin "4") (pinfunction "G_4") (pintype "passive"))
    )
    (net (code "23") (name "GH_B") (class "Default")
      (node (ref "U$2") (pin "42") (pinfunction "GH_B_42") (pintype "passive"))
      (node (ref "U$4") (pin "4") (pinfunction "G_4") (pintype "passive"))
    )
    (net (code "24") (name "GH_C") (class "Default")
      (node (ref "U$2") (pin "37") (pinfunction "GH_C_37") (pintype "passive"))
      (node (ref "U$5") (pin "4") (pinfunction "G_4") (pintype "passive"))
    )
    (net (code "25") (name "GL_A") (class "Default")
      (node (ref "U$2") (pin "45") (pinfunction "GL_A_45") (pintype "passive"))
      (node (ref "U$6") (pin "4") (pinfunction "G_4") (pintype "passive"))
    )
    (net (code "26") (name "GL_B") (class "Default")
      (node (ref "U$2") (pin "40") (pinfunction "GL_B_40") (pintype "passive"))
      (node (ref "U$7") (pin "4") (pinfunction "G_4") (pintype "passive"))
    )
    (net (code "27") (name "GL_C") (class "Default")
      (node (ref "U$2") (pin "35") (pinfunction "GL_C_35") (pintype "passive"))
      (node (ref "U$8") (pin "4") (pinfunction "G_4") (pintype "passive"))
    )
    (net (code "28") (name "GND") (class "Default")
      (node (ref "C20") (pin "2") (pinfunction "2_2") (pintype "passive"))
      (node (ref "C21") (pin "2") (pinfunction "2_2") (pintype "passive"))
      (node (ref "C22") (pin "1") (pinfunction "1_1") (pintype "passive"))
      (node (ref "C23") (pin "1") (pinfunction "1_1") (pintype "passive"))
      (node (ref "C24") (pin "2") (pinfunction "2_2") (pintype "passive"))
      (node (ref "C25") (pin "2") (pinfunction "2_2") (pintype "passive"))
      (node (ref "C26") (pin "2") (pinfunction "2_2") (pintype "passive"))
      (node (ref "C30") (pin "1") (pinfunction "1_1") (pintype "passive"))
      (node (ref "C31") (pin "2") (pinfunction "2_2") (pintype "passive"))
      (node (ref "C7") (pin "2") (pinfunction "2_2") (pintype "passive"))
      (node (ref "JP2") (pin "6") (pinfunction "6_6") (pintype "passive"))
      (node (ref "JP3") (pin "3") (pinfunction "3_3") (pintype "passive"))
      (node (ref "JP5") (pin "2") (pinfunction "2_2") (pintype "passive"))
      (node (ref "JP6") (pin "3") (pinfunction "3_3") (pintype "passive"))
      (node (ref "LED1") (pin "2") (pinfunction "C_2") (pintype "passive"))
      (node (ref "LED2") (pin "2") (pinfunction "C_2") (pintype "passive"))
      (node (ref "LED3") (pin "2") (pinfunction "C_2") (pintype "passive"))
      (node (ref "LED4") (pin "2") (pinfunction "C_2") (pintype "passive"))
      (node (ref "R19") (pin "2") (pinfunction "2_2") (pintype "passive"))
      (node (ref "U$1") (pin "20") (pinfunction "AVSS_20") (pintype "passive"))
      (node (ref "U$1") (pin "25") (pinfunction "VSS_3_25") (pintype "passive"))
      (node (ref "U$1") (pin "41") (pinfunction "VSS_41") (pintype "passive"))
      (node (ref "U$1") (pin "9") (pinfunction "VSS_2_9") (pintype "passive"))
      (node (ref "U1") (pin "4") (pinfunction "GND_4") (pintype "passive"))
      (node (ref "U1") (pin "5") (pinfunction "PGND_5") (pintype "passive"))
      (node (ref "U2") (pin "2") (pinfunction "GND_2") (pintype "passive"))
      (node (ref "U3") (pin "12") (pinfunction "GND_12") (pintype "passive"))
      (node (ref "U3") (pin "9") (pinfunction "*EN_9") (pintype "passive"))
      (node (ref "U9") (pin "1") (pinfunction "P$1_1") (pintype "bidirectional"))
    )
    (net (code "29") (name "MCLR") (class "Default")
      (node (ref "JP3") (pin "1") (pinfunction "1_1") (pintype "passive"))
      (node (ref "R5") (pin "1") (pinfunction "1_1") (pintype "passive"))
      (node (ref "U$1") (pin "7") (pinfunction "*MCLR_7") (pintype "passive"))
    )
    (net (code "30") (name "MISO") (class "Default")
      (node (ref "TP3") (pin "TP") (pinfunction "TP_TP") (pintype "input"))
      (node (ref "U$1") (pin "50") (pinfunction "RP54/RC6_50") (pintype "passive"))
      (node (ref "U$2") (pin "10") (pinfunction "SDO_10") (pintype "passive"))
    )
    (net (code "31") (name "MOSI") (class "Default")
      (node (ref "TP2") (pin "TP") (pinfunction "TP_TP") (pintype "input"))
      (node (ref "U$1") (pin "51") (pinfunction "RP55/RC7_51") (pintype "passive"))
      (node (ref "U$2") (pin "9") (pinfunction "SDI_9") (pintype "passive"))
    )
    (net (code "32") (name "Net-(C7-Pad1)") (class "Default")
      (node (ref "C7") (pin "1") (pinfunction "1_1") (pintype "passive"))
      (node (ref "R5") (pin "2") (pinfunction "2_2") (pintype "passive"))
      (node (ref "R6") (pin "2") (pinfunction "2_2") (pintype "passive"))
    )
    (net (code "33") (name "Net-(C15-Pad2)") (class "Default")
      (node (ref "C15") (pin "2") (pinfunction "2_2") (pintype "passive"))
      (node (ref "R9") (pin "2") (pinfunction "2_2") (pintype "passive"))
    )
    (net (code "34") (name "Net-(C28-Pad1)") (class "Default")
      (node (ref "C28") (pin "1") (pinfunction "1_1") (pintype "passive"))
      (node (ref "R20") (pin "1") (pinfunction "1_1") (pintype "passive"))
    )
    (net (code "35") (name "Net-(L1-1)") (class "Default")
      (node (ref "C6") (pin "2") (pinfunction "2_2") (pintype "passive"))
      (node (ref "D1") (pin "C") (pinfunction "C_C") (pintype "passive"))
      (node (ref "L1") (pin "P$1") (pinfunction "1_P$1") (pintype "passive"))
      (node (ref "U$2") (pin "50") (pinfunction "PH_50") (pintype "passive"))
      (node (ref "U$2") (pin "51") (pinfunction "PH_2_51") (pintype "passive"))
    )
    (net (code "36") (name "Net-(LED1-A)") (class "Default")
      (node (ref "LED1") (pin "1") (pinfunction "A_1") (pintype "passive"))
      (node (ref "RN1") (pin "P$5") (pinfunction "5_P$5") (pintype "passive"))
    )
    (net (code "37") (name "Net-(LED2-A)") (class "Default")
      (node (ref "LED2") (pin "1") (pinfunction "A_1") (pintype "passive"))
      (node (ref "RN1") (pin "P$6") (pinfunction "6_P$6") (pintype "passive"))
    )
    (net (code "38") (name "Net-(LED3-A)") (class "Default")
      (node (ref "LED3") (pin "1") (pinfunction "A_1") (pintype "passive"))
      (node (ref "RN1") (pin "P$7") (pinfunction "7_P$7") (pintype "passive"))
    )
    (net (code "39") (name "Net-(LED4-A)") (class "Default")
      (node (ref "LED4") (pin "1") (pinfunction "A_1") (pintype "passive"))
      (node (ref "RN1") (pin "P$8") (pinfunction "8_P$8") (pintype "passive"))
    )
    (net (code "40") (name "Net-(R17-Pad1)") (class "Default")
      (node (ref "R17") (pin "1") (pinfunction "1_1") (pintype "passive"))
      (node (ref "SJ8") (pin "1") (pinfunction "1_1") (pintype "passive"))
    )
    (net (code "41") (name "Net-(RN1-1)") (class "Default")
      (node (ref "RN1") (pin "P$1") (pinfunction "1_P$1") (pintype "passive"))
      (node (ref "U$1") (pin "48") (pinfunction "TCK/CVREF1O/ASCL1/RP40/T4CK/RB8_48") (pintype "passive"))
    )
    (net (code "42") (name "Net-(RN1-2)") (class "Default")
      (node (ref "RN1") (pin "P$2") (pinfunction "2_P$2") (pintype "passive"))
      (node (ref "U$1") (pin "47") (pinfunction "RC13_47") (pintype "passive"))
    )
    (net (code "43") (name "Net-(RN1-3)") (class "Default")
      (node (ref "RN1") (pin "P$3") (pinfunction "3_P$3") (pintype "passive"))
      (node (ref "U$1") (pin "46") (pinfunction "RP39/INT0/RB7_46") (pintype "passive"))
    )
    (net (code "44") (name "Net-(RN1-4)") (class "Default")
      (node (ref "RN1") (pin "P$4") (pinfunction "4_P$4") (pintype "passive"))
      (node (ref "U$1") (pin "45") (pinfunction "RPI58/RC10_45") (pintype "passive"))
    )
    (net (code "45") (name "Net-(U$1-AN6{slash}OA3OUT{slash}C4IN1+{slash}OCFB{slash}RC0)") (class "Default")
      (node (ref "JP2") (pin "3") (pinfunction "3_3") (pintype "passive"))
      (node (ref "U$1") (pin "21") (pinfunction "AN6/OA3OUT/C4IN1+/OCFB/RC0_21") (pintype "passive"))
    )
    (net (code "46") (name "Net-(U$1-AN7{slash}C3IN1-{slash}C4IN1-{slash}RC1)") (class "Default")
      (node (ref "JP2") (pin "4") (pinfunction "4_4") (pintype "passive"))
      (node (ref "U$1") (pin "22") (pinfunction "AN7/C3IN1-/C4IN1-/RC1_22") (pintype "passive"))
    )
    (net (code "47") (name "Net-(U$1-AN8{slash}C3IN1+{slash}*U1RTS{slash}BCLK1{slash}FLT3{slash}RC2)") (class "Default")
      (node (ref "JP2") (pin "5") (pinfunction "5_5") (pintype "passive"))
      (node (ref "U$1") (pin "23") (pinfunction "AN8/C3IN1+/*U1RTS/BCLK1/FLT3/RC2_23") (pintype "passive"))
    )
    (net (code "48") (name "Net-(U$1-AN12{slash}C2IN2-{slash}*U2RTS{slash}BCLK2{slash}RE12)") (class "Default")
      (node (ref "JP1") (pin "1") (pinfunction "1_1") (pintype "passive"))
      (node (ref "U$1") (pin "27") (pinfunction "AN12/C2IN2-/*U2RTS/BCLK2/RE12_27") (pintype "passive"))
    )
    (net (code "49") (name "Net-(U$1-AN13{slash}C3IN2-{slash}*U2CTS{slash}RE13)") (class "Default")
      (node (ref "JP1") (pin "2") (pinfunction "2_2") (pintype "passive"))
      (node (ref "U$1") (pin "28") (pinfunction "AN13/C3IN2-/*U2CTS/RE13_28") (pintype "passive"))
    )
    (net (code "50") (name "Net-(U$1-AN14{slash}RPI94{slash}RE14)") (class "Default")
      (node (ref "JP1") (pin "3") (pinfunction "3_3") (pintype "passive"))
      (node (ref "U$1") (pin "29") (pinfunction "AN14/RPI94/RE14_29") (pintype "passive"))
    )
    (net (code "51") (name "Net-(U$1-AN15{slash}RPI95{slash}RE15)") (class "Default")
      (node (ref "JP1") (pin "4") (pinfunction "4_4") (pintype "passive"))
      (node (ref "U$1") (pin "30") (pinfunction "AN15/RPI95/RE15_30") (pintype "passive"))
    )
    (net (code "52") (name "Net-(U$1-FLT32{slash}SCL2{slash}RP36{slash}RB4)") (class "Default")
      (node (ref "JP1") (pin "6") (pinfunction "6_6") (pintype "passive"))
      (node (ref "U$1") (pin "32") (pinfunction "FLT32/SCL2/RP36/RB4_32") (pintype "passive"))
    )
    (net (code "53") (name "Net-(U$1-PGEC3{slash}VREF+{slash}AN3{slash}OA1OUT{slash}RPI33{slash}CTED1{slash}RB1)") (class "Default")
      (node (ref "JP2") (pin "2") (pinfunction "2_2") (pintype "passive"))
      (node (ref "U$1") (pin "16") (pinfunction "PGEC3/VREF+/AN3/OA1OUT/RPI33/CTED1/RB1_16") (pintype "passive"))
    )
    (net (code "54") (name "Net-(U$1-PGED3{slash}VREF-{slash}AN2{slash}C2IN1-{slash}*SS1{slash}RPI32{slash}CTED2{slash}RB0)") (class "Default")
      (node (ref "R18") (pin "2") (pinfunction "2_2") (pintype "passive"))
      (node (ref "R19") (pin "1") (pinfunction "1_1") (pintype "passive"))
      (node (ref "U$1") (pin "15") (pinfunction "PGED3/VREF-/AN2/C2IN1-/*SS1/RPI32/CTED2/RB0_15") (pintype "passive"))
    )
    (net (code "55") (name "Net-(U$1-RP118{slash}RG6)") (class "Default")
      (node (ref "SJ4") (pin "2") (pinfunction "2_2") (pintype "passive"))
      (node (ref "U$1") (pin "4") (pinfunction "RP118/RG6_4") (pintype "passive"))
    )
    (net (code "56") (name "Net-(U$1-RP120{slash}RG8)") (class "Default")
      (node (ref "SJ6") (pin "2") (pinfunction "2_2") (pintype "passive"))
      (node (ref "U$1") (pin "6") (pinfunction "RP120/RG8_6") (pintype "passive"))
    )
    (net (code "57") (name "Net-(U$1-RPI119{slash}RG7)") (class "Default")
      (node (ref "SJ5") (pin "2") (pinfunction "2_2") (pintype "passive"))
      (node (ref "U$1") (pin "5") (pinfunction "RPI119/RG7_5") (pintype "passive"))
    )
    (net (code "58") (name "Net-(U$1-RPI121{slash}RG9)") (class "Default")
      (node (ref "SJ7") (pin "2") (pinfunction "2_2") (pintype "passive"))
      (node (ref "U$1") (pin "8") (pinfunction "RPI121/RG9_8") (pintype "passive"))
    )
    (net (code "59") (name "Net-(U$1-SDA2{slash}RPI24{slash}RA8)") (class "Default")
      (node (ref "JP1") (pin "5") (pinfunction "5_5") (pintype "passive"))
      (node (ref "U$1") (pin "31") (pinfunction "SDA2/RPI24/RA8_31") (pintype "passive"))
    )
    (net (code "60") (name "Net-(U$1-TDI{slash}RA7)") (class "Default")
      (node (ref "SJ1") (pin "2") (pinfunction "2_2") (pintype "passive"))
      (node (ref "U$1") (pin "1") (pinfunction "TDI/RA7_1") (pintype "passive"))
    )
    (net (code "61") (name "Net-(U$1-VCAP)") (class "Default")
      (node (ref "C20") (pin "1") (pinfunction "1_1") (pintype "passive"))
      (node (ref "U$1") (pin "56") (pinfunction "VCAP_56") (pintype "passive"))
    )
    (net (code "62") (name "Net-(U$2-*FAULT)") (class "Default")
      (node (ref "TP7") (pin "TP") (pinfunction "TP_TP") (pintype "input"))
      (node (ref "U$2") (pin "6") (pinfunction "*FAULT_6") (pintype "passive"))
    )
    (net (code "63") (name "Net-(U$2-*OCTW)") (class "Default")
      (node (ref "TP6") (pin "TP") (pinfunction "TP_TP") (pintype "input"))
      (node (ref "U$2") (pin "5") (pinfunction "*OCTW_5") (pintype "passive"))
    )
    (net (code "64") (name "Net-(U$2-AVDD)") (class "Default")
      (node (ref "C19") (pin "2") (pinfunction "2_2") (pintype "passive"))
      (node (ref "U$2") (pin "27") (pinfunction "AVDD_27") (pintype "passive"))
    )
    (net (code "65") (name "Net-(U$2-BST_A)") (class "Default")
      (node (ref "C9") (pin "1") (pinfunction "1_1") (pintype "passive"))
      (node (ref "U$2") (pin "48") (pinfunction "BST_A_48") (pintype "passive"))
    )
    (net (code "66") (name "Net-(U$2-BST_B)") (class "Default")
      (node (ref "C10") (pin "1") (pinfunction "1_1") (pintype "passive"))
      (node (ref "U$2") (pin "43") (pinfunction "BST_B_43") (pintype "passive"))
    )
    (net (code "67") (name "Net-(U$2-BST_BK)") (class "Default")
      (node (ref "C6") (pin "1") (pinfunction "1_1") (pintype "passive"))
      (node (ref "U$2") (pin "52") (pinfunction "BST_BK_52") (pintype "passive"))
    )
    (net (code "68") (name "Net-(U$2-BST_C)") (class "Default")
      (node (ref "C11") (pin "1") (pinfunction "1_1") (pintype "passive"))
      (node (ref "U$2") (pin "38") (pinfunction "BST_C_38") (pintype "passive"))
    )
    (net (code "69") (name "Net-(U$2-COMP)") (class "Default")
      (node (ref "C14") (pin "2") (pinfunction "2_2") (pintype "passive"))
      (node (ref "R9") (pin "1") (pinfunction "1_1") (pintype "passive"))
      (node (ref "U$2") (pin "2") (pinfunction "COMP_2") (pintype "passive"))
    )
    (net (code "70") (name "Net-(U$2-CP1)") (class "Default")
      (node (ref "C17") (pin "1") (pinfunction "1_1") (pintype "passive"))
      (node (ref "U$2") (pin "14") (pinfunction "CP1_14") (pintype "passive"))
    )
    (net (code "71") (name "Net-(U$2-CP2)") (class "Default")
      (node (ref "C17") (pin "2") (pinfunction "2_2") (pintype "passive"))
      (node (ref "U$2") (pin "15") (pinfunction "CP2_15") (pintype "passive"))
    )
    (net (code "72") (name "Net-(U$2-DVDD)") (class "Default")
      (node (ref "C18") (pin "2") (pinfunction "2_2") (pintype "passive"))
      (node (ref "U$2") (pin "23") (pinfunction "DVDD_23") (pintype "passive"))
    )
    (net (code "73") (name "Net-(U$2-EN_BUCK)") (class "Default")
      (node (ref "SJ2") (pin "1") (pinfunction "1_1") (pintype "passive"))
      (node (ref "U$2") (pin "55") (pinfunction "EN_BUCK_55") (pintype "passive"))
    )
    (net (code "74") (name "Net-(U$2-GVDD)") (class "Default")
      (node (ref "C16") (pin "1") (pinfunction "1_1") (pintype "passive"))
      (node (ref "U$2") (pin "13") (pinfunction "GVDD_13") (pintype "passive"))
    )
    (net (code "75") (name "Net-(U$2-PWRGD)") (class "Default")
      (node (ref "TP5") (pin "TP") (pinfunction "TP_TP") (pintype "input"))
      (node (ref "U$2") (pin "4") (pinfunction "PWRGD_4") (pintype "passive"))
    )
    (net (code "76") (name "Net-(U$2-RT_CLK)") (class "Default")
      (node (ref "R8") (pin "1") (pinfunction "1_1") (pintype "passive"))
      (node (ref "U$2") (pin "1") (pinfunction "RT_CLK_1") (pintype "passive"))
    )
    (net (code "77") (name "Net-(U$2-SS_TR)") (class "Default")
      (node (ref "C5") (pin "1") (pinfunction "1_1") (pintype "passive"))
      (node (ref "U$2") (pin "56") (pinfunction "SS_TR_56") (pintype "passive"))
    )
    (net (code "78") (name "Net-(U$2-VSENSE)") (class "Default")
      (node (ref "R10") (pin "1") (pinfunction "1_1") (pintype "passive"))
      (node (ref "R11") (pin "2") (pinfunction "2_2") (pintype "passive"))
      (node (ref "U$2") (pin "3") (pinfunction "VSENSE_3") (pintype "passive"))
    )
    (net (code "79") (name "Net-(U1-CPUMP+)") (class "Default")
      (node (ref "C29") (pin "1") (pinfunction "1_1") (pintype "passive"))
      (node (ref "U1") (pin "7") (pinfunction "CPUMP+_7") (pintype "passive"))
    )
    (net (code "80") (name "Net-(U1-CPUMP-)") (class "Default")
      (node (ref "C29") (pin "2") (pinfunction "2_2") (pintype "passive"))
      (node (ref "U1") (pin "6") (pinfunction "CPUMP-_6") (pintype "passive"))
    )
    (net (code "81") (name "PGC") (class "Default")
      (node (ref "JP3") (pin "5") (pinfunction "5_5") (pintype "passive"))
      (node (ref "U$1") (pin "44") (pinfunction "PGEC2/ASCL2/RP38/RB6_44") (pintype "passive"))
    )
    (net (code "82") (name "PGD") (class "Default")
      (node (ref "JP3") (pin "4") (pinfunction "4_4") (pintype "passive"))
      (node (ref "U$1") (pin "43") (pinfunction "PGED2/ASDA2/RP37/RB5_43") (pintype "passive"))
    )
    (net (code "83") (name "PGND") (class "Default")
      (node (ref "C12") (pin "2") (pinfunction "2_2") (pintype "passive"))
      (node (ref "C13") (pin "2") (pinfunction "2_2") (pintype "passive"))
      (node (ref "C27") (pin "2") (pinfunction "-_2") (pintype "passive"))
      (node (ref "C28") (pin "2") (pinfunction "2_2") (pintype "passive"))
      (node (ref "J2") (pin "1") (pinfunction "2_1") (pintype "passive"))
      (node (ref "R4") (pin "1") (pinfunction "1_1") (pintype "passive"))
      (node (ref "R7") (pin "1") (pinfunction "1_1") (pintype "passive"))
      (node (ref "U$7") (pin "1") (pinfunction "S_1") (pintype "passive"))
      (node (ref "U$7") (pin "2") (pinfunction "S_2") (pintype "passive"))
      (node (ref "U$7") (pin "3") (pinfunction "S_3") (pintype "passive"))
      (node (ref "U10") (pin "2") (pinfunction "P$2_2") (pintype "bidirectional"))
      (node (ref "U11") (pin "2") (pinfunction "P$2_2") (pintype "bidirectional"))
      (node (ref "U13") (pin "2") (pinfunction "P$2_2") (pintype "bidirectional"))
      (node (ref "U14") (pin "2") (pinfunction "P$2_2") (pintype "bidirectional"))
    )
    (net (code "84") (name "PVDD") (class "Default")
      (node (ref "C1") (pin "1") (pinfunction "1_1") (pintype "passive"))
      (node (ref "C2") (pin "1") (pinfunction "1_1") (pintype "passive"))
      (node (ref "C27") (pin "1") (pinfunction "+_1") (pintype "passive"))
      (node (ref "C3") (pin "1") (pinfunction "1_1") (pintype "passive"))
      (node (ref "C4") (pin "1") (pinfunction "1_1") (pintype "passive"))
      (node (ref "J2") (pin "2") (pinfunction "1_2") (pintype "passive"))
      (node (ref "JP2") (pin "1") (pinfunction "1_1") (pintype "passive"))
      (node (ref "R18") (pin "1") (pinfunction "1_1") (pintype "passive"))
      (node (ref "R20") (pin "2") (pinfunction "2_2") (pintype "passive"))
      (node (ref "U$2") (pin "29") (pinfunction "PVDD1_29") (pintype "passive"))
      (node (ref "U$2") (pin "53") (pinfunction "PVDD2_53") (pintype "passive"))
      (node (ref "U$2") (pin "54") (pinfunction "PVDD2_2_54") (pintype "passive"))
      (node (ref "U$3") (pin "5") (pinfunction "D_5") (pintype "passive"))
      (node (ref "U$3") (pin "P$1") (pinfunction "D_P$1") (pintype "passive"))
      (node (ref "U$3") (pin "P$2") (pinfunction "D_P$2") (pintype "passive"))
      (node (ref "U$3") (pin "P$3") (pinfunction "D_P$3") (pintype "passive"))
      (node (ref "U$3") (pin "P$4") (pinfunction "D_P$4") (pintype "passive"))
      (node (ref "U$3") (pin "P$5") (pinfunction "D_P$5") (pintype "passive"))
      (node (ref "U$3") (pin "P$6") (pinfunction "D_P$6") (pintype "passive"))
      (node (ref "U$3") (pin "P$7") (pinfunction "D_P$7") (pintype "passive"))
      (node (ref "U$3") (pin "P$8") (pinfunction "D_P$8") (pintype "passive"))
      (node (ref "U$3") (pin "P$9") (pinfunction "D_P$9") (pintype "passive"))
      (node (ref "U$4") (pin "5") (pinfunction "D_5") (pintype "passive"))
      (node (ref "U$4") (pin "P$1") (pinfunction "D_P$1") (pintype "passive"))
      (node (ref "U$4") (pin "P$2") (pinfunction "D_P$2") (pintype "passive"))
      (node (ref "U$4") (pin "P$3") (pinfunction "D_P$3") (pintype "passive"))
      (node (ref "U$4") (pin "P$4") (pinfunction "D_P$4") (pintype "passive"))
      (node (ref "U$4") (pin "P$5") (pinfunction "D_P$5") (pintype "passive"))
      (node (ref "U$4") (pin "P$6") (pinfunction "D_P$6") (pintype "passive"))
      (node (ref "U$4") (pin "P$7") (pinfunction "D_P$7") (pintype "passive"))
      (node (ref "U$4") (pin "P$8") (pinfunction "D_P$8") (pintype "passive"))
      (node (ref "U$4") (pin "P$9") (pinfunction "D_P$9") (pintype "passive"))
      (node (ref "U$5") (pin "5") (pinfunction "D_5") (pintype "passive"))
      (node (ref "U$5") (pin "P$1") (pinfunction "D_P$1") (pintype "passive"))
      (node (ref "U$5") (pin "P$2") (pinfunction "D_P$2") (pintype "passive"))
      (node (ref "U$5") (pin "P$3") (pinfunction "D_P$3") (pintype "passive"))
      (node (ref "U$5") (pin "P$4") (pinfunction "D_P$4") (pintype "passive"))
      (node (ref "U$5") (pin "P$5") (pinfunction "D_P$5") (pintype "passive"))
      (node (ref "U$5") (pin "P$6") (pinfunction "D_P$6") (pintype "passive"))
      (node (ref "U$5") (pin "P$7") (pinfunction "D_P$7") (pintype "passive"))
      (node (ref "U$5") (pin "P$8") (pinfunction "D_P$8") (pintype "passive"))
      (node (ref "U$5") (pin "P$9") (pinfunction "D_P$9") (pintype "passive"))
    )
    (net (code "85") (name "PWM1H") (class "Default")
      (node (ref "U$1") (pin "2") (pinfunction "RPI46/PWM1H/T3CK/RB14_2") (pintype "passive"))
      (node (ref "U$2") (pin "17") (pinfunction "INH_A_17") (pintype "passive"))
    )
    (net (code "86") (name "PWM1L") (class "Default")
      (node (ref "U$1") (pin "3") (pinfunction "RPI47/PWM1L/T5CK/RB15_3") (pintype "passive"))
      (node (ref "U$2") (pin "18") (pinfunction "INL_A_18") (pintype "passive"))
    )
    (net (code "87") (name "PWM2H") (class "Default")
      (node (ref "U$1") (pin "62") (pinfunction "RPI44/PWM2H/RB12_62") (pintype "passive"))
      (node (ref "U$2") (pin "19") (pinfunction "INH_B_19") (pintype "passive"))
    )
    (net (code "88") (name "PWM2L") (class "Default")
      (node (ref "U$1") (pin "63") (pinfunction "RPI45/PWM2L/CTPLS/RB13_63") (pintype "passive"))
      (node (ref "U$2") (pin "20") (pinfunction "INL_B_20") (pintype "passive"))
    )
    (net (code "89") (name "PWM3H") (class "Default")
      (node (ref "U$1") (pin "60") (pinfunction "RP42/PWM3H/RB10_60") (pintype "passive"))
      (node (ref "U$2") (pin "21") (pinfunction "INH_C_21") (pintype "passive"))
    )
    (net (code "90") (name "PWM3L") (class "Default")
      (node (ref "U$1") (pin "61") (pinfunction "RB43/PWM3L/RB11_61") (pintype "passive"))
      (node (ref "U$2") (pin "22") (pinfunction "INL_C_22") (pintype "passive"))
    )
    (net (code "91") (name "RA11") (class "Default")
      (node (ref "JP5") (pin "3") (pinfunction "3_3") (pintype "passive"))
      (node (ref "U$1") (pin "12") (pinfunction "AN9/RPI27/RA11_12") (pintype "passive"))
    )
    (net (code "92") (name "RA12") (class "Default")
      (node (ref "U$1") (pin "11") (pinfunction "AN10/RPI28/RA12_11") (pintype "passive"))
    )
    (net (code "93") (name "SCLK") (class "Default")
      (node (ref "TP4") (pin "TP") (pinfunction "TP_TP") (pintype "input"))
      (node (ref "U$1") (pin "49") (pinfunction "TMS/ASDA1/RP41/RB9_49") (pintype "passive"))
      (node (ref "U$2") (pin "11") (pinfunction "SCLK_11") (pintype "passive"))
    )
    (net (code "94") (name "SH_A") (class "Default")
      (node (ref "C9") (pin "2") (pinfunction "2_2") (pintype "passive"))
      (node (ref "JP7") (pin "3") (pinfunction "3_3") (pintype "passive"))
      (node (ref "U$2") (pin "46") (pinfunction "SH_A_46") (pintype "passive"))
      (node (ref "U$3") (pin "1") (pinfunction "S_1") (pintype "passive"))
      (node (ref "U$3") (pin "2") (pinfunction "S_2") (pintype "passive"))
      (node (ref "U$3") (pin "3") (pinfunction "S_3") (pintype "passive"))
      (node (ref "U$6") (pin "5") (pinfunction "D_5") (pintype "passive"))
      (node (ref "U$6") (pin "P$1") (pinfunction "D_P$1") (pintype "passive"))
      (node (ref "U$6") (pin "P$2") (pinfunction "D_P$2") (pintype "passive"))
      (node (ref "U$6") (pin "P$3") (pinfunction "D_P$3") (pintype "passive"))
      (node (ref "U$6") (pin "P$4") (pinfunction "D_P$4") (pintype "passive"))
      (node (ref "U$6") (pin "P$5") (pinfunction "D_P$5") (pintype "passive"))
      (node (ref "U$6") (pin "P$6") (pinfunction "D_P$6") (pintype "passive"))
      (node (ref "U$6") (pin "P$7") (pinfunction "D_P$7") (pintype "passive"))
      (node (ref "U$6") (pin "P$8") (pinfunction "D_P$8") (pintype "passive"))
      (node (ref "U$6") (pin "P$9") (pinfunction "D_P$9") (pintype "passive"))
    )
    (net (code "95") (name "SH_B") (class "Default")
      (node (ref "C10") (pin "2") (pinfunction "2_2") (pintype "passive"))
      (node (ref "JP7") (pin "2") (pinfunction "2_2") (pintype "passive"))
      (node (ref "U$2") (pin "41") (pinfunction "SH_B_41") (pintype "passive"))
      (node (ref "U$4") (pin "1") (pinfunction "S_1") (pintype "passive"))
      (node (ref "U$4") (pin "2") (pinfunction "S_2") (pintype "passive"))
      (node (ref "U$4") (pin "3") (pinfunction "S_3") (pintype "passive"))
      (node (ref "U$7") (pin "5") (pinfunction "D_5") (pintype "passive"))
      (node (ref "U$7") (pin "P$1") (pinfunction "D_P$1") (pintype "passive"))
      (node (ref "U$7") (pin "P$2") (pinfunction "D_P$2") (pintype "passive"))
      (node (ref "U$7") (pin "P$3") (pinfunction "D_P$3") (pintype "passive"))
      (node (ref "U$7") (pin "P$4") (pinfunction "D_P$4") (pintype "passive"))
      (node (ref "U$7") (pin "P$5") (pinfunction "D_P$5") (pintype "passive"))
      (node (ref "U$7") (pin "P$6") (pinfunction "D_P$6") (pintype "passive"))
      (node (ref "U$7") (pin "P$7") (pinfunction "D_P$7") (pintype "passive"))
      (node (ref "U$7") (pin "P$8") (pinfunction "D_P$8") (pintype "passive"))
      (node (ref "U$7") (pin "P$9") (pinfunction "D_P$9") (pintype "passive"))
    )
    (net (code "96") (name "SH_C") (class "Default")
      (node (ref "C11") (pin "2") (pinfunction "2_2") (pintype "passive"))
      (node (ref "JP7") (pin "1") (pinfunction "1_1") (pintype "passive"))
      (node (ref "U$2") (pin "36") (pinfunction "SH_C_36") (pintype "passive"))
      (node (ref "U$5") (pin "1") (pinfunction "S_1") (pintype "passive"))
      (node (ref "U$5") (pin "2") (pinfunction "S_2") (pintype "passive"))
      (node (ref "U$5") (pin "3") (pinfunction "S_3") (pintype "passive"))
      (node (ref "U$8") (pin "5") (pinfunction "D_5") (pintype "passive"))
      (node (ref "U$8") (pin "P$1") (pinfunction "D_P$1") (pintype "passive"))
      (node (ref "U$8") (pin "P$2") (pinfunction "D_P$2") (pintype "passive"))
      (node (ref "U$8") (pin "P$3") (pinfunction "D_P$3") (pintype "passive"))
      (node (ref "U$8") (pin "P$4") (pinfunction "D_P$4") (pintype "passive"))
      (node (ref "U$8") (pin "P$5") (pinfunction "D_P$5") (pintype "passive"))
      (node (ref "U$8") (pin "P$6") (pinfunction "D_P$6") (pintype "passive"))
      (node (ref "U$8") (pin "P$7") (pinfunction "D_P$7") (pintype "passive"))
      (node (ref "U$8") (pin "P$8") (pinfunction "D_P$8") (pintype "passive"))
      (node (ref "U$8") (pin "P$9") (pinfunction "D_P$9") (pintype "passive"))
    )
    (net (code "97") (name "SL_A") (class "Default")
      (node (ref "U$2") (pin "44") (pinfunction "SL_A_44") (pintype "passive"))
      (node (ref "U12") (pin "2") (pinfunction "P$2_2") (pintype "bidirectional"))
    )
    (net (code "98") (name "SL_B") (class "Default")
      (node (ref "U$2") (pin "39") (pinfunction "SL_B_39") (pintype "passive"))
      (node (ref "U11") (pin "1") (pinfunction "P$1_1") (pintype "bidirectional"))
    )
    (net (code "99") (name "SL_C") (class "Default")
      (node (ref "U$2") (pin "34") (pinfunction "SL_C_34") (pintype "passive"))
      (node (ref "U15") (pin "2") (pinfunction "P$2_2") (pintype "bidirectional"))
    )
    (net (code "100") (name "SN1") (class "Default")
      (node (ref "C12") (pin "1") (pinfunction "1_1") (pintype "passive"))
      (node (ref "R7") (pin "2") (pinfunction "2_2") (pintype "passive"))
      (node (ref "U$2") (pin "33") (pinfunction "SN1_33") (pintype "passive"))
      (node (ref "U$6") (pin "1") (pinfunction "S_1") (pintype "passive"))
      (node (ref "U$6") (pin "2") (pinfunction "S_2") (pintype "passive"))
      (node (ref "U$6") (pin "3") (pinfunction "S_3") (pintype "passive"))
      (node (ref "U12") (pin "1") (pinfunction "P$1_1") (pintype "bidirectional"))
    )
    (net (code "101") (name "SN2") (class "Default")
      (node (ref "C13") (pin "1") (pinfunction "1_1") (pintype "passive"))
      (node (ref "R4") (pin "2") (pinfunction "2_2") (pintype "passive"))
      (node (ref "U$2") (pin "31") (pinfunction "SN2_31") (pintype "passive"))
      (node (ref "U$8") (pin "1") (pinfunction "S_1") (pintype "passive"))
      (node (ref "U$8") (pin "2") (pinfunction "S_2") (pintype "passive"))
      (node (ref "U$8") (pin "3") (pinfunction "S_3") (pintype "passive"))
      (node (ref "U15") (pin "1") (pinfunction "P$1_1") (pintype "bidirectional"))
    )
    (net (code "102") (name "SP1") (class "Default")
      (node (ref "U$2") (pin "32") (pinfunction "SP1_32") (pintype "passive"))
      (node (ref "U13") (pin "1") (pinfunction "P$1_1") (pintype "bidirectional"))
    )
    (net (code "103") (name "SP2") (class "Default")
      (node (ref "U$2") (pin "30") (pinfunction "SP2_30") (pintype "passive"))
      (node (ref "U14") (pin "1") (pinfunction "P$1_1") (pintype "bidirectional"))
    )
    (net (code "104") (name "VCC3V3") (class "Default")
      (node (ref "C21") (pin "1") (pinfunction "1_1") (pintype "passive"))
      (node (ref "C22") (pin "2") (pinfunction "2_2") (pintype "passive"))
      (node (ref "C23") (pin "2") (pinfunction "2_2") (pintype "passive"))
      (node (ref "C24") (pin "1") (pinfunction "1_1") (pintype "passive"))
      (node (ref "C25") (pin "1") (pinfunction "1_1") (pintype "passive"))
      (node (ref "C26") (pin "1") (pinfunction "1_1") (pintype "passive"))
      (node (ref "C31") (pin "1") (pinfunction "1_1") (pintype "passive"))
      (node (ref "C8") (pin "1") (pinfunction "1_1") (pintype "passive"))
      (node (ref "JP3") (pin "2") (pinfunction "2_2") (pintype "passive"))
      (node (ref "JP5") (pin "1") (pinfunction "1_1") (pintype "passive"))
      (node (ref "L1") (pin "P$2") (pinfunction "2_P$2") (pintype "passive"))
      (node (ref "R10") (pin "2") (pinfunction "2_2") (pintype "passive"))
      (node (ref "R6") (pin "1") (pinfunction "1_1") (pintype "passive"))
      (node (ref "SJ1") (pin "1") (pinfunction "1_1") (pintype "passive"))
      (node (ref "SJ4") (pin "1") (pinfunction "1_1") (pintype "passive"))
      (node (ref "SJ5") (pin "1") (pinfunction "1_1") (pintype "passive"))
      (node (ref "SJ6") (pin "1") (pinfunction "1_1") (pintype "passive"))
      (node (ref "SJ7") (pin "1") (pinfunction "1_1") (pintype "passive"))
      (node (ref "U$1") (pin "10") (pinfunction "VDD_2_10") (pintype "passive"))
      (node (ref "U$1") (pin "19") (pinfunction "AVDD_19") (pintype "passive"))
      (node (ref "U$1") (pin "26") (pinfunction "VDD_3_26") (pintype "passive"))
      (node (ref "U$1") (pin "38") (pinfunction "VDD_4_38") (pintype "passive"))
      (node (ref "U$1") (pin "57") (pinfunction "VDD_57") (pintype "passive"))
      (node (ref "U$2") (pin "24") (pinfunction "REF_24") (pintype "passive"))
      (node (ref "U$2") (pin "49") (pinfunction "VDD_SPI_49") (pintype "passive"))
      (node (ref "U1") (pin "2") (pinfunction "ENABLE_2") (pintype "passive"))
      (node (ref "U1") (pin "3") (pinfunction "VIN_3") (pintype "passive"))
      (node (ref "U2") (pin "3") (pinfunction "VCC_3") (pintype "passive"))
      (node (ref "U3") (pin "13") (pinfunction "VCC_13") (pintype "passive"))
      (node (ref "U3") (pin "16") (pinfunction "EN_16") (pintype "passive"))
    )
    (net (code "105") (name "VCC5V") (class "Default")
      (node (ref "C30") (pin "2") (pinfunction "2_2") (pintype "passive"))
      (node (ref "JP5") (pin "6") (pinfunction "6_6") (pintype "passive"))
      (node (ref "U1") (pin "8") (pinfunction "VOUT_8") (pintype "passive"))
    )
    (net (code "106") (name "unconnected-(JP3-Pad6)") (class "Default")
      (node (ref "JP3") (pin "6") (pinfunction "6_6") (pintype "passive"))
    )
    (net (code "107") (name "unconnected-(U$1-AN11{slash}C1IN2-{slash}*U1CTS{slash}FLT4{slash}RC11-Pad24)") (class "Default")
      (node (ref "U$1") (pin "24") (pinfunction "AN11/C1IN2-/*U1CTS/FLT4/RC11_24") (pintype "passive"))
    )
    (net (code "108") (name "unconnected-(U$1-CVREF2O{slash}SDO1{slash}RP20{slash}T1CK{slash}RA4-Pad33)") (class "Default")
      (node (ref "U$1") (pin "33") (pinfunction "CVREF2O/SDO1/RP20/T1CK/RA4_33") (pintype "passive"))
    )
    (net (code "109") (name "unconnected-(U$1-OSC1{slash}CLKI{slash}RC12-Pad39)") (class "Default")
      (node (ref "U$1") (pin "39") (pinfunction "OSC1/CLKI/RC12_39") (pintype "passive"))
    )
    (net (code "110") (name "unconnected-(U$1-OSC2{slash}CLKO{slash}RC15-Pad40)") (class "Default")
      (node (ref "U$1") (pin "40") (pinfunction "OSC2/CLKO/RC15_40") (pintype "passive"))
    )
    (net (code "111") (name "unconnected-(U$1-RD8-Pad42)") (class "Default")
      (node (ref "U$1") (pin "42") (pinfunction "RD8_42") (pintype "passive"))
    )
    (net (code "112") (name "unconnected-(U$1-RP57{slash}RC9-Pad55)") (class "Default")
      (node (ref "U$1") (pin "55") (pinfunction "RP57/RC9_55") (pintype "passive"))
    )
    (net (code "113") (name "unconnected-(U$1-SCL1{slash}RPI53{slash}RC5-Pad37)") (class "Default")
      (node (ref "U$1") (pin "37") (pinfunction "SCL1/RPI53/RC5_37") (pintype "passive"))
    )
    (net (code "114") (name "unconnected-(U$1-TDO{slash}RA10-Pad64)") (class "Default")
      (node (ref "U$1") (pin "64") (pinfunction "TDO/RA10_64") (pintype "passive"))
    )
    (net (code "115") (name "unconnected-(U1-NC-Pad1)") (class "Default")
      (node (ref "U1") (pin "1") (pinfunction "NC_1") (pintype "passive"))
    )
    (net (code "116") (name "unconnected-(U2-NC-Pad8)") (class "Default")
      (node (ref "U2") (pin "8") (pinfunction "NC_8") (pintype "passive"))
    )
    (net (code "117") (name "unconnected-(U2-NC_2-Pad5)") (class "Default")
      (node (ref "U2") (pin "5") (pinfunction "NC_2_5") (pintype "passive"))
    )
    (net (code "118") (name "unconnected-(U3-RIN4+-Pad7)") (class "Default")
      (node (ref "U3") (pin "7") (pinfunction "RIN4+_7") (pintype "passive"))
    )
    (net (code "119") (name "unconnected-(U3-RIN4-Pad8)") (class "Default")
      (node (ref "U3") (pin "8") (pinfunction "RIN4_8") (pintype "passive"))
    )
    (net (code "120") (name "unconnected-(U3-ROUT4-Pad10)") (class "Default")
      (node (ref "U3") (pin "10") (pinfunction "ROUT4_10") (pintype "passive"))
    )
  )
)
